# HHKB.net
KiCad netlist of a schematic drawn in EAGLE
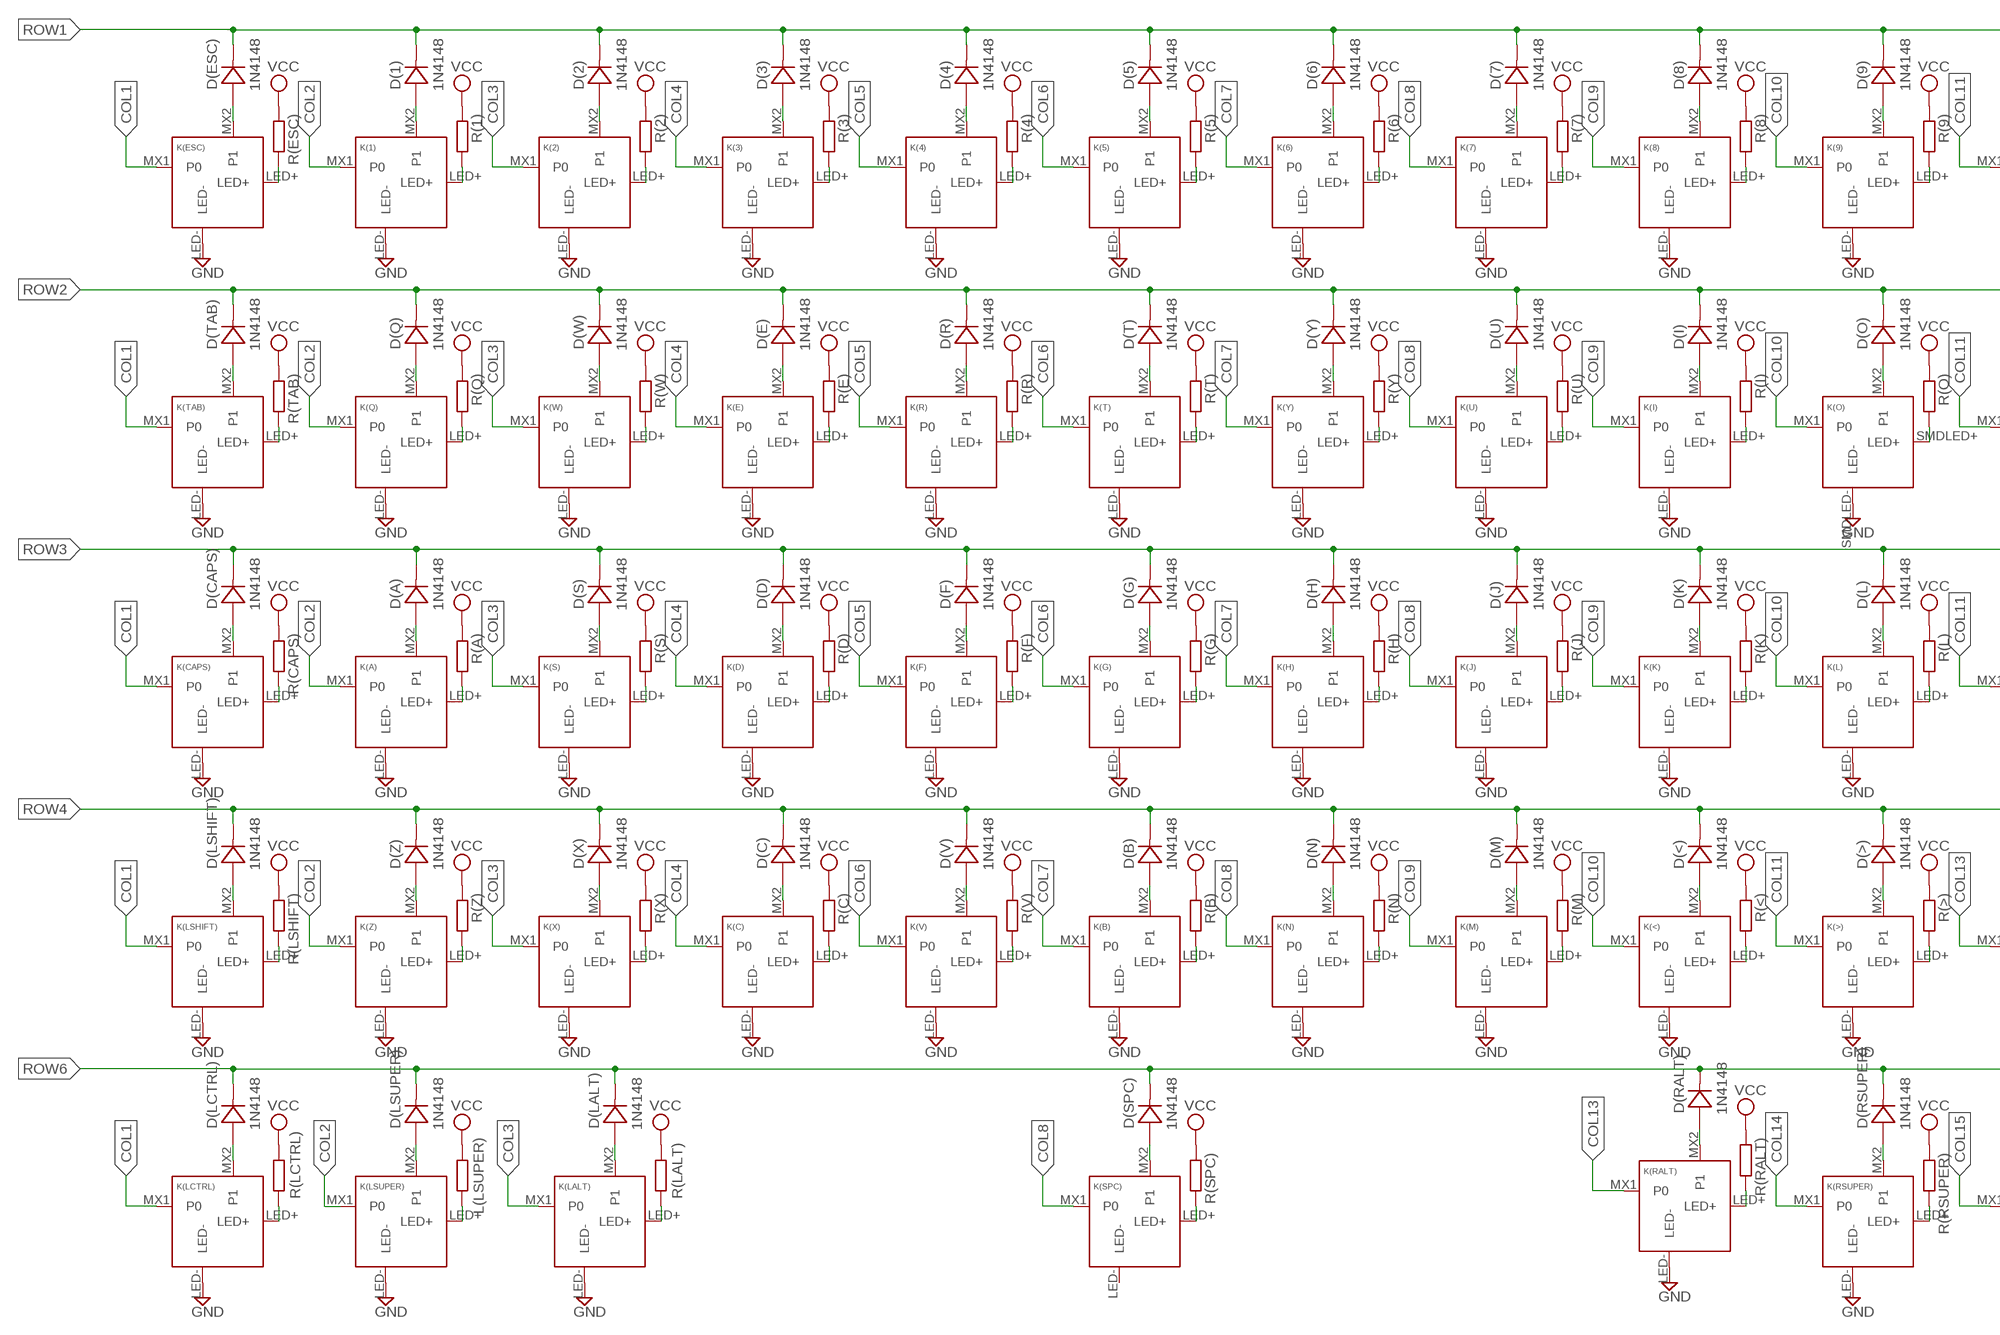
[diagram p0: schematic, sheet 1, part 1 of 2]
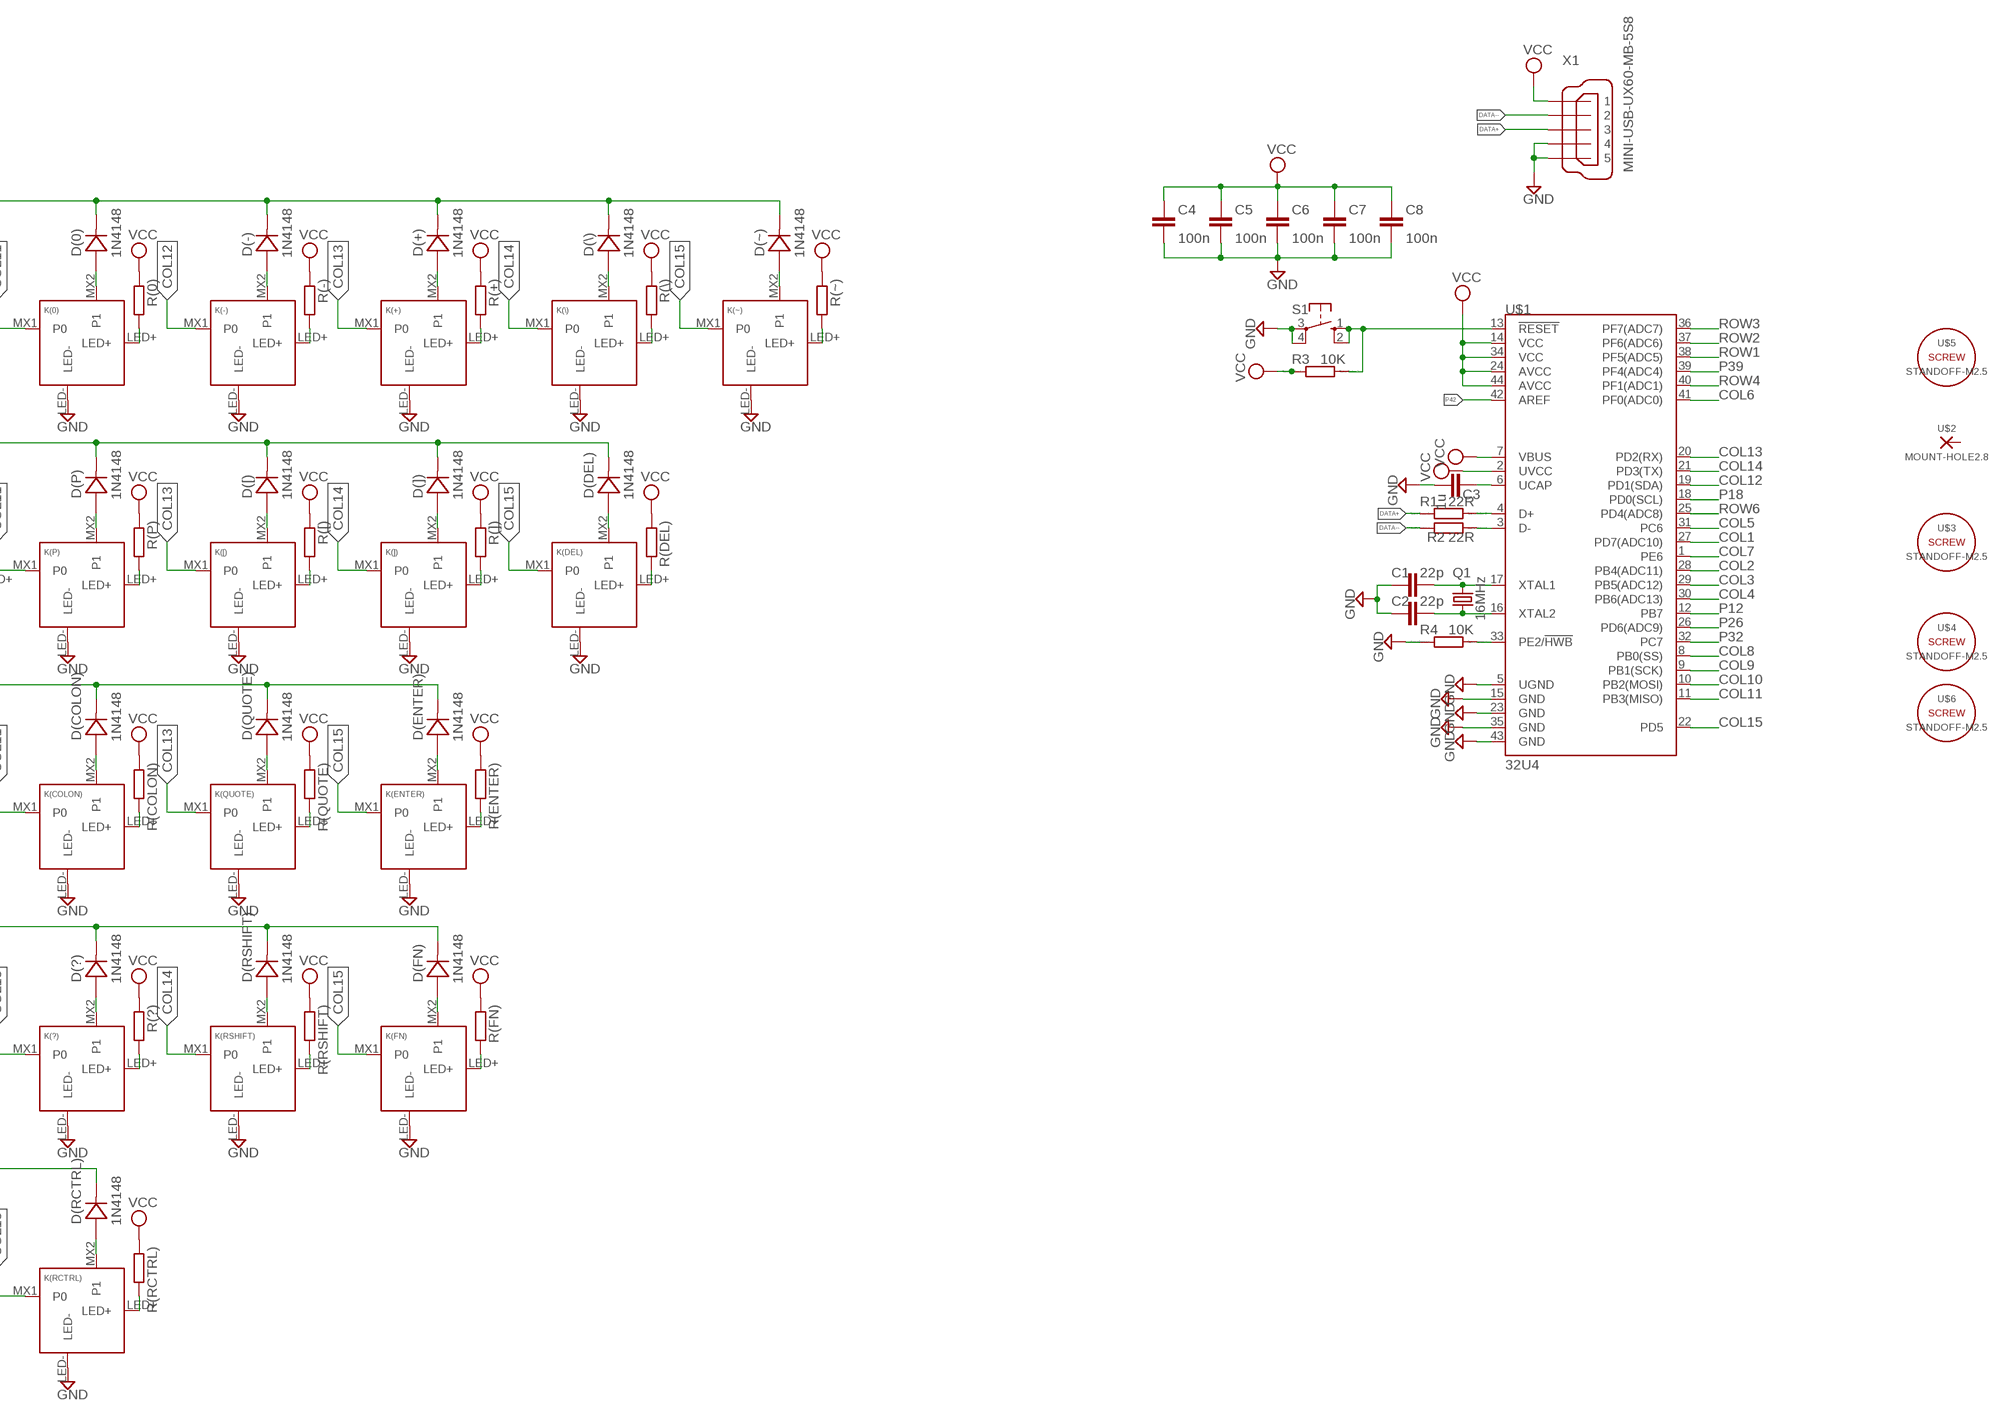
[diagram p1: schematic, sheet 1, part 2 of 2]

(export (version "E")
  (design (tool "Eeschema 10.0.6"))
  (components
    (comp (ref "C1")
      (value "22p")
      (footprint "eagle-import:C0805K")
      (libsource (lib "eagle-import") (part "C-EUC0805K"))
    )
    (comp (ref "C2")
      (value "22p")
      (footprint "eagle-import:C0805K")
      (libsource (lib "eagle-import") (part "C-EUC0805K"))
    )
    (comp (ref "C3")
      (value "1u")
      (footprint "eagle-import:C0805K")
      (libsource (lib "eagle-import") (part "C-EUC0805K"))
    )
    (comp (ref "C4")
      (value "100n")
      (footprint "eagle-import:C0805K")
      (libsource (lib "eagle-import") (part "C-EUC0805K"))
    )
    (comp (ref "C5")
      (value "100n")
      (footprint "eagle-import:C0805K")
      (libsource (lib "eagle-import") (part "C-EUC0805K"))
    )
    (comp (ref "C6")
      (value "100n")
      (footprint "eagle-import:C0805K")
      (libsource (lib "eagle-import") (part "C-EUC0805K"))
    )
    (comp (ref "C7")
      (value "100n")
      (footprint "eagle-import:C0805K")
      (libsource (lib "eagle-import") (part "C-EUC0805K"))
    )
    (comp (ref "C8")
      (value "100n")
      (footprint "eagle-import:C0805K")
      (libsource (lib "eagle-import") (part "C-EUC0805K"))
    )
    (comp (ref "D(+)")
      (value "1N4148")
      (footprint "eagle-import:DIODE_HAND")
      (libsource (lib "eagle-import") (part "DIODE-HAND"))
    )
    (comp (ref "D(-)")
      (value "1N4148")
      (footprint "eagle-import:DIODE_HAND")
      (libsource (lib "eagle-import") (part "DIODE-HAND"))
    )
    (comp (ref "D(0)")
      (value "1N4148")
      (footprint "eagle-import:DIODE_HAND")
      (libsource (lib "eagle-import") (part "DIODE-HAND"))
    )
    (comp (ref "D(1)")
      (value "1N4148")
      (footprint "eagle-import:DIODE_HAND")
      (libsource (lib "eagle-import") (part "DIODE-HAND"))
    )
    (comp (ref "D(2)")
      (value "1N4148")
      (footprint "eagle-import:DIODE_HAND")
      (libsource (lib "eagle-import") (part "DIODE-HAND"))
    )
    (comp (ref "D(3)")
      (value "1N4148")
      (footprint "eagle-import:DIODE_HAND")
      (libsource (lib "eagle-import") (part "DIODE-HAND"))
    )
    (comp (ref "D(4)")
      (value "1N4148")
      (footprint "eagle-import:DIODE_HAND")
      (libsource (lib "eagle-import") (part "DIODE-HAND"))
    )
    (comp (ref "D(5)")
      (value "1N4148")
      (footprint "eagle-import:DIODE_HAND")
      (libsource (lib "eagle-import") (part "DIODE-HAND"))
    )
    (comp (ref "D(6)")
      (value "1N4148")
      (footprint "eagle-import:DIODE_HAND")
      (libsource (lib "eagle-import") (part "DIODE-HAND"))
    )
    (comp (ref "D(7)")
      (value "1N4148")
      (footprint "eagle-import:DIODE_HAND")
      (libsource (lib "eagle-import") (part "DIODE-HAND"))
    )
    (comp (ref "D(8)")
      (value "1N4148")
      (footprint "eagle-import:DIODE_HAND")
      (libsource (lib "eagle-import") (part "DIODE-HAND"))
    )
    (comp (ref "D(9)")
      (value "1N4148")
      (footprint "eagle-import:DIODE_HAND")
      (libsource (lib "eagle-import") (part "DIODE-HAND"))
    )
    (comp (ref "D(<)")
      (value "1N4148")
      (footprint "eagle-import:DIODE_HAND")
      (libsource (lib "eagle-import") (part "DIODE-HAND"))
    )
    (comp (ref "D(>)")
      (value "1N4148")
      (footprint "eagle-import:DIODE_HAND")
      (libsource (lib "eagle-import") (part "DIODE-HAND"))
    )
    (comp (ref "D(?)")
      (value "1N4148")
      (footprint "eagle-import:DIODE_HAND")
      (libsource (lib "eagle-import") (part "DIODE-HAND"))
    )
    (comp (ref "D(A)")
      (value "1N4148")
      (footprint "eagle-import:DIODE_HAND")
      (libsource (lib "eagle-import") (part "DIODE-HAND"))
    )
    (comp (ref "D(B)")
      (value "1N4148")
      (footprint "eagle-import:DIODE_HAND")
      (libsource (lib "eagle-import") (part "DIODE-HAND"))
    )
    (comp (ref "D(C)")
      (value "1N4148")
      (footprint "eagle-import:DIODE_HAND")
      (libsource (lib "eagle-import") (part "DIODE-HAND"))
    )
    (comp (ref "D(CAPS)")
      (value "1N4148")
      (footprint "eagle-import:DIODE_HAND")
      (libsource (lib "eagle-import") (part "DIODE-HAND"))
    )
    (comp (ref "D(COLON)")
      (value "1N4148")
      (footprint "eagle-import:DIODE_HAND")
      (libsource (lib "eagle-import") (part "DIODE-HAND"))
    )
    (comp (ref "D(D)")
      (value "1N4148")
      (footprint "eagle-import:DIODE_HAND")
      (libsource (lib "eagle-import") (part "DIODE-HAND"))
    )
    (comp (ref "D(DEL)")
      (value "1N4148")
      (footprint "eagle-import:DIODE_HAND")
      (libsource (lib "eagle-import") (part "DIODE-HAND"))
    )
    (comp (ref "D(E)")
      (value "1N4148")
      (footprint "eagle-import:DIODE_HAND")
      (libsource (lib "eagle-import") (part "DIODE-HAND"))
    )
    (comp (ref "D(ENTER)")
      (value "1N4148")
      (footprint "eagle-import:DIODE_HAND")
      (libsource (lib "eagle-import") (part "DIODE-HAND"))
    )
    (comp (ref "D(ESC)")
      (value "1N4148")
      (footprint "eagle-import:DIODE_HAND")
      (libsource (lib "eagle-import") (part "DIODE-HAND"))
    )
    (comp (ref "D(F)")
      (value "1N4148")
      (footprint "eagle-import:DIODE_HAND")
      (libsource (lib "eagle-import") (part "DIODE-HAND"))
    )
    (comp (ref "D(FN)")
      (value "1N4148")
      (footprint "eagle-import:DIODE_HAND")
      (libsource (lib "eagle-import") (part "DIODE-HAND"))
    )
    (comp (ref "D(G)")
      (value "1N4148")
      (footprint "eagle-import:DIODE_HAND")
      (libsource (lib "eagle-import") (part "DIODE-HAND"))
    )
    (comp (ref "D(H)")
      (value "1N4148")
      (footprint "eagle-import:DIODE_HAND")
      (libsource (lib "eagle-import") (part "DIODE-HAND"))
    )
    (comp (ref "D(I)")
      (value "1N4148")
      (footprint "eagle-import:DIODE_HAND")
      (libsource (lib "eagle-import") (part "DIODE-HAND"))
    )
    (comp (ref "D(J)")
      (value "1N4148")
      (footprint "eagle-import:DIODE_HAND")
      (libsource (lib "eagle-import") (part "DIODE-HAND"))
    )
    (comp (ref "D(K)")
      (value "1N4148")
      (footprint "eagle-import:DIODE_HAND")
      (libsource (lib "eagle-import") (part "DIODE-HAND"))
    )
    (comp (ref "D(L)")
      (value "1N4148")
      (footprint "eagle-import:DIODE_HAND")
      (libsource (lib "eagle-import") (part "DIODE-HAND"))
    )
    (comp (ref "D(LALT)")
      (value "1N4148")
      (footprint "eagle-import:DIODE_HAND")
      (libsource (lib "eagle-import") (part "DIODE-HAND"))
    )
    (comp (ref "D(LCTRL)")
      (value "1N4148")
      (footprint "eagle-import:DIODE_HAND")
      (libsource (lib "eagle-import") (part "DIODE-HAND"))
    )
    (comp (ref "D(LSHIFT)")
      (value "1N4148")
      (footprint "eagle-import:DIODE_HAND")
      (libsource (lib "eagle-import") (part "DIODE-HAND"))
    )
    (comp (ref "D(LSUPER)")
      (value "1N4148")
      (footprint "eagle-import:DIODE_HAND")
      (libsource (lib "eagle-import") (part "DIODE-HAND"))
    )
    (comp (ref "D(M)")
      (value "1N4148")
      (footprint "eagle-import:DIODE_HAND")
      (libsource (lib "eagle-import") (part "DIODE-HAND"))
    )
    (comp (ref "D(N)")
      (value "1N4148")
      (footprint "eagle-import:DIODE_HAND")
      (libsource (lib "eagle-import") (part "DIODE-HAND"))
    )
    (comp (ref "D(O)")
      (value "1N4148")
      (footprint "eagle-import:DIODE_HAND")
      (libsource (lib "eagle-import") (part "DIODE-HAND"))
    )
    (comp (ref "D(P)")
      (value "1N4148")
      (footprint "eagle-import:DIODE_HAND")
      (libsource (lib "eagle-import") (part "DIODE-HAND"))
    )
    (comp (ref "D(Q)")
      (value "1N4148")
      (footprint "eagle-import:DIODE_HAND")
      (libsource (lib "eagle-import") (part "DIODE-HAND"))
    )
    (comp (ref "D(QUOTE)")
      (value "1N4148")
      (footprint "eagle-import:DIODE_HAND")
      (libsource (lib "eagle-import") (part "DIODE-HAND"))
    )
    (comp (ref "D(R)")
      (value "1N4148")
      (footprint "eagle-import:DIODE_HAND")
      (libsource (lib "eagle-import") (part "DIODE-HAND"))
    )
    (comp (ref "D(RALT)")
      (value "1N4148")
      (footprint "eagle-import:DIODE_HAND")
      (libsource (lib "eagle-import") (part "DIODE-HAND"))
    )
    (comp (ref "D(RCTRL)")
      (value "1N4148")
      (footprint "eagle-import:DIODE_HAND")
      (libsource (lib "eagle-import") (part "DIODE-HAND"))
    )
    (comp (ref "D(RSHIFT)")
      (value "1N4148")
      (footprint "eagle-import:DIODE_HAND")
      (libsource (lib "eagle-import") (part "DIODE-HAND"))
    )
    (comp (ref "D(RSUPER)")
      (value "1N4148")
      (footprint "eagle-import:DIODE_HAND")
      (libsource (lib "eagle-import") (part "DIODE-HAND"))
    )
    (comp (ref "D(S)")
      (value "1N4148")
      (footprint "eagle-import:DIODE_HAND")
      (libsource (lib "eagle-import") (part "DIODE-HAND"))
    )
    (comp (ref "D(SPC)")
      (value "1N4148")
      (footprint "eagle-import:DIODE_HAND")
      (libsource (lib "eagle-import") (part "DIODE-HAND"))
    )
    (comp (ref "D(T)")
      (value "1N4148")
      (footprint "eagle-import:DIODE_HAND")
      (libsource (lib "eagle-import") (part "DIODE-HAND"))
    )
    (comp (ref "D(TAB)")
      (value "1N4148")
      (footprint "eagle-import:DIODE_HAND")
      (libsource (lib "eagle-import") (part "DIODE-HAND"))
    )
    (comp (ref "D(U)")
      (value "1N4148")
      (footprint "eagle-import:DIODE_HAND")
      (libsource (lib "eagle-import") (part "DIODE-HAND"))
    )
    (comp (ref "D(V)")
      (value "1N4148")
      (footprint "eagle-import:DIODE_HAND")
      (libsource (lib "eagle-import") (part "DIODE-HAND"))
    )
    (comp (ref "D(W)")
      (value "1N4148")
      (footprint "eagle-import:DIODE_HAND")
      (libsource (lib "eagle-import") (part "DIODE-HAND"))
    )
    (comp (ref "D(X)")
      (value "1N4148")
      (footprint "eagle-import:DIODE_HAND")
      (libsource (lib "eagle-import") (part "DIODE-HAND"))
    )
    (comp (ref "D(Y)")
      (value "1N4148")
      (footprint "eagle-import:DIODE_HAND")
      (libsource (lib "eagle-import") (part "DIODE-HAND"))
    )
    (comp (ref "D(Z)")
      (value "1N4148")
      (footprint "eagle-import:DIODE_HAND")
      (libsource (lib "eagle-import") (part "DIODE-HAND"))
    )
    (comp (ref "D([)")
      (value "1N4148")
      (footprint "eagle-import:DIODE_HAND")
      (libsource (lib "eagle-import") (part "DIODE-HAND"))
    )
    (comp (ref "D(\\\\)")
      (value "1N4148")
      (footprint "eagle-import:DIODE_HAND")
      (libsource (lib "eagle-import") (part "DIODE-HAND"))
    )
    (comp (ref "D(])")
      (value "1N4148")
      (footprint "eagle-import:DIODE_HAND")
      (libsource (lib "eagle-import") (part "DIODE-HAND"))
    )
    (comp (ref "D(~)")
      (value "1N4148")
      (footprint "eagle-import:DIODE_HAND")
      (libsource (lib "eagle-import") (part "DIODE-HAND"))
    )
    (comp (ref "K(+)")
      (value "KEYSWITCH-LEDTHTHOLE-MXHS-1U-LEDTHTHOLE")
      (footprint "eagle-import:MXHS-1U-LEDTHTHOLE")
      (libsource (lib "eagle-import") (part "KEYSWITCH-LEDTHTHOLE-MXHS-1U-LEDTHTHOLE"))
    )
    (comp (ref "K(-)")
      (value "KEYSWITCH-LEDTHTHOLE-MXHS-1U-LEDTHTHOLE")
      (footprint "eagle-import:MXHS-1U-LEDTHTHOLE")
      (libsource (lib "eagle-import") (part "KEYSWITCH-LEDTHTHOLE-MXHS-1U-LEDTHTHOLE"))
    )
    (comp (ref "K(0)")
      (value "KEYSWITCH-LEDTHTHOLE-MXHS-1U-LEDTHTHOLE")
      (footprint "eagle-import:MXHS-1U-LEDTHTHOLE")
      (libsource (lib "eagle-import") (part "KEYSWITCH-LEDTHTHOLE-MXHS-1U-LEDTHTHOLE"))
    )
    (comp (ref "K(1)")
      (value "KEYSWITCH-LEDTHTHOLE-MXHS-1U-LEDTHTHOLE")
      (footprint "eagle-import:MXHS-1U-LEDTHTHOLE")
      (libsource (lib "eagle-import") (part "KEYSWITCH-LEDTHTHOLE-MXHS-1U-LEDTHTHOLE"))
    )
    (comp (ref "K(2)")
      (value "KEYSWITCH-LEDTHTHOLE-MXHS-1U-LEDTHTHOLE")
      (footprint "eagle-import:MXHS-1U-LEDTHTHOLE")
      (libsource (lib "eagle-import") (part "KEYSWITCH-LEDTHTHOLE-MXHS-1U-LEDTHTHOLE"))
    )
    (comp (ref "K(3)")
      (value "KEYSWITCH-LEDTHTHOLE-MXHS-1U-LEDTHTHOLE")
      (footprint "eagle-import:MXHS-1U-LEDTHTHOLE")
      (libsource (lib "eagle-import") (part "KEYSWITCH-LEDTHTHOLE-MXHS-1U-LEDTHTHOLE"))
    )
    (comp (ref "K(4)")
      (value "KEYSWITCH-LEDTHTHOLE-MXHS-1U-LEDTHTHOLE")
      (footprint "eagle-import:MXHS-1U-LEDTHTHOLE")
      (libsource (lib "eagle-import") (part "KEYSWITCH-LEDTHTHOLE-MXHS-1U-LEDTHTHOLE"))
    )
    (comp (ref "K(5)")
      (value "KEYSWITCH-LEDTHTHOLE-MXHS-1U-LEDTHTHOLE")
      (footprint "eagle-import:MXHS-1U-LEDTHTHOLE")
      (libsource (lib "eagle-import") (part "KEYSWITCH-LEDTHTHOLE-MXHS-1U-LEDTHTHOLE"))
    )
    (comp (ref "K(6)")
      (value "KEYSWITCH-LEDTHTHOLE-MXHS-1U-LEDTHTHOLE")
      (footprint "eagle-import:MXHS-1U-LEDTHTHOLE")
      (libsource (lib "eagle-import") (part "KEYSWITCH-LEDTHTHOLE-MXHS-1U-LEDTHTHOLE"))
    )
    (comp (ref "K(7)")
      (value "KEYSWITCH-LEDTHTHOLE-MXHS-1U-LEDTHTHOLE")
      (footprint "eagle-import:MXHS-1U-LEDTHTHOLE")
      (libsource (lib "eagle-import") (part "KEYSWITCH-LEDTHTHOLE-MXHS-1U-LEDTHTHOLE"))
    )
    (comp (ref "K(8)")
      (value "KEYSWITCH-LEDTHTHOLE-MXHS-1U-LEDTHTHOLE")
      (footprint "eagle-import:MXHS-1U-LEDTHTHOLE")
      (libsource (lib "eagle-import") (part "KEYSWITCH-LEDTHTHOLE-MXHS-1U-LEDTHTHOLE"))
    )
    (comp (ref "K(9)")
      (value "KEYSWITCH-LEDTHTHOLE-MXHS-1U-LEDTHTHOLE")
      (footprint "eagle-import:MXHS-1U-LEDTHTHOLE")
      (libsource (lib "eagle-import") (part "KEYSWITCH-LEDTHTHOLE-MXHS-1U-LEDTHTHOLE"))
    )
    (comp (ref "K(<)")
      (value "KEYSWITCH-LEDTHTHOLE-MXHS-1U-LEDTHTHOLE")
      (footprint "eagle-import:MXHS-1U-LEDTHTHOLE")
      (libsource (lib "eagle-import") (part "KEYSWITCH-LEDTHTHOLE-MXHS-1U-LEDTHTHOLE"))
    )
    (comp (ref "K(>)")
      (value "KEYSWITCH-LEDTHTHOLE-MXHS-1U-LEDTHTHOLE")
      (footprint "eagle-import:MXHS-1U-LEDTHTHOLE")
      (libsource (lib "eagle-import") (part "KEYSWITCH-LEDTHTHOLE-MXHS-1U-LEDTHTHOLE"))
    )
    (comp (ref "K(?)")
      (value "KEYSWITCH-LEDTHTHOLE-MXHS-1U-LEDTHTHOLE")
      (footprint "eagle-import:MXHS-1U-LEDTHTHOLE")
      (libsource (lib "eagle-import") (part "KEYSWITCH-LEDTHTHOLE-MXHS-1U-LEDTHTHOLE"))
    )
    (comp (ref "K(A)")
      (value "KEYSWITCH-LEDTHTHOLE-MXHS-1U-LEDTHTHOLE")
      (footprint "eagle-import:MXHS-1U-LEDTHTHOLE")
      (libsource (lib "eagle-import") (part "KEYSWITCH-LEDTHTHOLE-MXHS-1U-LEDTHTHOLE"))
    )
    (comp (ref "K(B)")
      (value "KEYSWITCH-LEDTHTHOLE-MXHS-1U-LEDTHTHOLE")
      (footprint "eagle-import:MXHS-1U-LEDTHTHOLE")
      (libsource (lib "eagle-import") (part "KEYSWITCH-LEDTHTHOLE-MXHS-1U-LEDTHTHOLE"))
    )
    (comp (ref "K(C)")
      (value "KEYSWITCH-LEDTHTHOLE-MXHS-1U-LEDTHTHOLE")
      (footprint "eagle-import:MXHS-1U-LEDTHTHOLE")
      (libsource (lib "eagle-import") (part "KEYSWITCH-LEDTHTHOLE-MXHS-1U-LEDTHTHOLE"))
    )
    (comp (ref "K(CAPS)")
      (value "KEYSWITCH-LEDTHTHOLE-MXHS-1U-LEDTHTHOLE")
      (footprint "eagle-import:MXHS-1U-LEDTHTHOLE")
      (libsource (lib "eagle-import") (part "KEYSWITCH-LEDTHTHOLE-MXHS-1U-LEDTHTHOLE"))
    )
    (comp (ref "K(COLON)")
      (value "KEYSWITCH-LEDTHTHOLE-MXHS-1U-LEDTHTHOLE")
      (footprint "eagle-import:MXHS-1U-LEDTHTHOLE")
      (libsource (lib "eagle-import") (part "KEYSWITCH-LEDTHTHOLE-MXHS-1U-LEDTHTHOLE"))
    )
    (comp (ref "K(D)")
      (value "KEYSWITCH-LEDTHTHOLE-MXHS-1U-LEDTHTHOLE")
      (footprint "eagle-import:MXHS-1U-LEDTHTHOLE")
      (libsource (lib "eagle-import") (part "KEYSWITCH-LEDTHTHOLE-MXHS-1U-LEDTHTHOLE"))
    )
    (comp (ref "K(DEL)")
      (value "KEYSWITCH-LEDTHTHOLE-MXHS-1U-LEDTHTHOLE")
      (footprint "eagle-import:MXHS-1U-LEDTHTHOLE")
      (libsource (lib "eagle-import") (part "KEYSWITCH-LEDTHTHOLE-MXHS-1U-LEDTHTHOLE"))
    )
    (comp (ref "K(E)")
      (value "KEYSWITCH-LEDTHTHOLE-MXHS-1U-LEDTHTHOLE")
      (footprint "eagle-import:MXHS-1U-LEDTHTHOLE")
      (libsource (lib "eagle-import") (part "KEYSWITCH-LEDTHTHOLE-MXHS-1U-LEDTHTHOLE"))
    )
    (comp (ref "K(ENTER)")
      (value "KEYSWITCH-LEDTHTHOLE-MXHS-2U-LEDTHTHOLE")
      (footprint "eagle-import:MXHS-2U-LEDTHTHOLE")
      (libsource (lib "eagle-import") (part "KEYSWITCH-LEDTHTHOLE-MXHS-2U-LEDTHTHOLE"))
    )
    (comp (ref "K(ESC)")
      (value "KEYSWITCH-LEDTHTHOLE-MXHS-1U-LEDTHTHOLE")
      (footprint "eagle-import:MXHS-1U-LEDTHTHOLE")
      (libsource (lib "eagle-import") (part "KEYSWITCH-LEDTHTHOLE-MXHS-1U-LEDTHTHOLE"))
    )
    (comp (ref "K(F)")
      (value "KEYSWITCH-LEDTHTHOLE-MXHS-1U-LEDTHTHOLE")
      (footprint "eagle-import:MXHS-1U-LEDTHTHOLE")
      (libsource (lib "eagle-import") (part "KEYSWITCH-LEDTHTHOLE-MXHS-1U-LEDTHTHOLE"))
    )
    (comp (ref "K(FN)")
      (value "KEYSWITCH-LEDTHTHOLE-MXHS-1U-LEDTHTHOLE")
      (footprint "eagle-import:MXHS-1U-LEDTHTHOLE")
      (libsource (lib "eagle-import") (part "KEYSWITCH-LEDTHTHOLE-MXHS-1U-LEDTHTHOLE"))
    )
    (comp (ref "K(G)")
      (value "KEYSWITCH-LEDTHTHOLE-MXHS-1U-LEDTHTHOLE")
      (footprint "eagle-import:MXHS-1U-LEDTHTHOLE")
      (libsource (lib "eagle-import") (part "KEYSWITCH-LEDTHTHOLE-MXHS-1U-LEDTHTHOLE"))
    )
    (comp (ref "K(H)")
      (value "KEYSWITCH-LEDTHTHOLE-MXHS-1U-LEDTHTHOLE")
      (footprint "eagle-import:MXHS-1U-LEDTHTHOLE")
      (libsource (lib "eagle-import") (part "KEYSWITCH-LEDTHTHOLE-MXHS-1U-LEDTHTHOLE"))
    )
    (comp (ref "K(I)")
      (value "KEYSWITCH-LEDTHTHOLE-MXHS-1U-LEDTHTHOLE")
      (footprint "eagle-import:MXHS-1U-LEDTHTHOLE")
      (libsource (lib "eagle-import") (part "KEYSWITCH-LEDTHTHOLE-MXHS-1U-LEDTHTHOLE"))
    )
    (comp (ref "K(J)")
      (value "KEYSWITCH-LEDTHTHOLE-MXHS-1U-LEDTHTHOLE")
      (footprint "eagle-import:MXHS-1U-LEDTHTHOLE")
      (libsource (lib "eagle-import") (part "KEYSWITCH-LEDTHTHOLE-MXHS-1U-LEDTHTHOLE"))
    )
    (comp (ref "K(K)")
      (value "KEYSWITCH-LEDTHTHOLE-MXHS-1U-LEDTHTHOLE")
      (footprint "eagle-import:MXHS-1U-LEDTHTHOLE")
      (libsource (lib "eagle-import") (part "KEYSWITCH-LEDTHTHOLE-MXHS-1U-LEDTHTHOLE"))
    )
    (comp (ref "K(L)")
      (value "KEYSWITCH-LEDTHTHOLE-MXHS-1U-LEDTHTHOLE")
      (footprint "eagle-import:MXHS-1U-LEDTHTHOLE")
      (libsource (lib "eagle-import") (part "KEYSWITCH-LEDTHTHOLE-MXHS-1U-LEDTHTHOLE"))
    )
    (comp (ref "K(LALT)")
      (value "KEYSWITCH-LEDTHTHOLE-MXHS-1U-LEDTHTHOLE")
      (footprint "eagle-import:MXHS-1U-LEDTHTHOLE")
      (libsource (lib "eagle-import") (part "KEYSWITCH-LEDTHTHOLE-MXHS-1U-LEDTHTHOLE"))
    )
    (comp (ref "K(LCTRL)")
      (value "KEYSWITCH-LEDTHTHOLE-MXHS-1U-LEDTHTHOLE")
      (footprint "eagle-import:MXHS-1U-LEDTHTHOLE")
      (libsource (lib "eagle-import") (part "KEYSWITCH-LEDTHTHOLE-MXHS-1U-LEDTHTHOLE"))
    )
    (comp (ref "K(LSHIFT)")
      (value "KEYSWITCH-LEDTHTHOLE-MXHS-2U-LEDTHTHOLE")
      (footprint "eagle-import:MXHS-2U-LEDTHTHOLE")
      (libsource (lib "eagle-import") (part "KEYSWITCH-LEDTHTHOLE-MXHS-2U-LEDTHTHOLE"))
    )
    (comp (ref "K(LSUPER)")
      (value "KEYSWITCH-LEDTHTHOLE-MXHS-1U-LEDTHTHOLE")
      (footprint "eagle-import:MXHS-1U-LEDTHTHOLE")
      (libsource (lib "eagle-import") (part "KEYSWITCH-LEDTHTHOLE-MXHS-1U-LEDTHTHOLE"))
    )
    (comp (ref "K(M)")
      (value "KEYSWITCH-LEDTHTHOLE-MXHS-1U-LEDTHTHOLE")
      (footprint "eagle-import:MXHS-1U-LEDTHTHOLE")
      (libsource (lib "eagle-import") (part "KEYSWITCH-LEDTHTHOLE-MXHS-1U-LEDTHTHOLE"))
    )
    (comp (ref "K(N)")
      (value "KEYSWITCH-LEDTHTHOLE-MXHS-1U-LEDTHTHOLE")
      (footprint "eagle-import:MXHS-1U-LEDTHTHOLE")
      (libsource (lib "eagle-import") (part "KEYSWITCH-LEDTHTHOLE-MXHS-1U-LEDTHTHOLE"))
    )
    (comp (ref "K(O)")
      (value "KEYSWITCH-SMDLED-MXHSPCB-1U-SMDLED")
      (footprint "eagle-import:MXHSPCB-1U-SMDLED")
      (libsource (lib "eagle-import") (part "KEYSWITCH-SMDLED-MXHSPCB-1U-SMDLED"))
    )
    (comp (ref "K(P)")
      (value "KEYSWITCH-LEDTHTHOLE-MXHS-1U-LEDTHTHOLE")
      (footprint "eagle-import:MXHS-1U-LEDTHTHOLE")
      (libsource (lib "eagle-import") (part "KEYSWITCH-LEDTHTHOLE-MXHS-1U-LEDTHTHOLE"))
    )
    (comp (ref "K(Q)")
      (value "KEYSWITCH-LEDTHTHOLE-MXHS-1U-LEDTHTHOLE")
      (footprint "eagle-import:MXHS-1U-LEDTHTHOLE")
      (libsource (lib "eagle-import") (part "KEYSWITCH-LEDTHTHOLE-MXHS-1U-LEDTHTHOLE"))
    )
    (comp (ref "K(QUOTE)")
      (value "KEYSWITCH-LEDTHTHOLE-MXHS-1U-LEDTHTHOLE")
      (footprint "eagle-import:MXHS-1U-LEDTHTHOLE")
      (libsource (lib "eagle-import") (part "KEYSWITCH-LEDTHTHOLE-MXHS-1U-LEDTHTHOLE"))
    )
    (comp (ref "K(R)")
      (value "KEYSWITCH-LEDTHTHOLE-MXHS-1U-LEDTHTHOLE")
      (footprint "eagle-import:MXHS-1U-LEDTHTHOLE")
      (libsource (lib "eagle-import") (part "KEYSWITCH-LEDTHTHOLE-MXHS-1U-LEDTHTHOLE"))
    )
    (comp (ref "K(RALT)")
      (value "KEYSWITCH-LEDTHTHOLE-MXHS-1U-LEDTHTHOLE")
      (footprint "eagle-import:MXHS-1U-LEDTHTHOLE")
      (libsource (lib "eagle-import") (part "KEYSWITCH-LEDTHTHOLE-MXHS-1U-LEDTHTHOLE"))
    )
    (comp (ref "K(RCTRL)")
      (value "KEYSWITCH-LEDTHTHOLE-MXHS-1U-LEDTHTHOLE")
      (footprint "eagle-import:MXHS-1U-LEDTHTHOLE")
      (libsource (lib "eagle-import") (part "KEYSWITCH-LEDTHTHOLE-MXHS-1U-LEDTHTHOLE"))
    )
    (comp (ref "K(RSHIFT)")
      (value "KEYSWITCH-LEDTHTHOLE-MXHS-1U-LEDTHTHOLE")
      (footprint "eagle-import:MXHS-1U-LEDTHTHOLE")
      (libsource (lib "eagle-import") (part "KEYSWITCH-LEDTHTHOLE-MXHS-1U-LEDTHTHOLE"))
    )
    (comp (ref "K(RSUPER)")
      (value "KEYSWITCH-LEDTHTHOLE-MXHS-1U-LEDTHTHOLE")
      (footprint "eagle-import:MXHS-1U-LEDTHTHOLE")
      (libsource (lib "eagle-import") (part "KEYSWITCH-LEDTHTHOLE-MXHS-1U-LEDTHTHOLE"))
    )
    (comp (ref "K(S)")
      (value "KEYSWITCH-LEDTHTHOLE-MXHS-1U-LEDTHTHOLE")
      (footprint "eagle-import:MXHS-1U-LEDTHTHOLE")
      (libsource (lib "eagle-import") (part "KEYSWITCH-LEDTHTHOLE-MXHS-1U-LEDTHTHOLE"))
    )
    (comp (ref "K(SPC)")
      (value "KEYSWITCH-LEDTHTHOLE-MXHS-7U-LEDTHTHOLE")
      (footprint "eagle-import:MXHS-7U-LEDTHTHOLE")
      (libsource (lib "eagle-import") (part "KEYSWITCH-LEDTHTHOLE-MXHS-7U-LEDTHTHOLE"))
    )
    (comp (ref "K(T)")
      (value "KEYSWITCH-LEDTHTHOLE-MXHS-1U-LEDTHTHOLE")
      (footprint "eagle-import:MXHS-1U-LEDTHTHOLE")
      (libsource (lib "eagle-import") (part "KEYSWITCH-LEDTHTHOLE-MXHS-1U-LEDTHTHOLE"))
    )
    (comp (ref "K(TAB)")
      (value "KEYSWITCH-LEDTHTHOLE-MXHS-1U-LEDTHTHOLE")
      (footprint "eagle-import:MXHS-1U-LEDTHTHOLE")
      (libsource (lib "eagle-import") (part "KEYSWITCH-LEDTHTHOLE-MXHS-1U-LEDTHTHOLE"))
    )
    (comp (ref "K(U)")
      (value "KEYSWITCH-LEDTHTHOLE-MXHS-1U-LEDTHTHOLE")
      (footprint "eagle-import:MXHS-1U-LEDTHTHOLE")
      (libsource (lib "eagle-import") (part "KEYSWITCH-LEDTHTHOLE-MXHS-1U-LEDTHTHOLE"))
    )
    (comp (ref "K(V)")
      (value "KEYSWITCH-LEDTHTHOLE-MXHS-1U-LEDTHTHOLE")
      (footprint "eagle-import:MXHS-1U-LEDTHTHOLE")
      (libsource (lib "eagle-import") (part "KEYSWITCH-LEDTHTHOLE-MXHS-1U-LEDTHTHOLE"))
    )
    (comp (ref "K(W)")
      (value "KEYSWITCH-LEDTHTHOLE-MXHS-1U-LEDTHTHOLE")
      (footprint "eagle-import:MXHS-1U-LEDTHTHOLE")
      (libsource (lib "eagle-import") (part "KEYSWITCH-LEDTHTHOLE-MXHS-1U-LEDTHTHOLE"))
    )
    (comp (ref "K(X)")
      (value "KEYSWITCH-LEDTHTHOLE-MXHS-1U-LEDTHTHOLE")
      (footprint "eagle-import:MXHS-1U-LEDTHTHOLE")
      (libsource (lib "eagle-import") (part "KEYSWITCH-LEDTHTHOLE-MXHS-1U-LEDTHTHOLE"))
    )
    (comp (ref "K(Y)")
      (value "KEYSWITCH-LEDTHTHOLE-MXHS-1U-LEDTHTHOLE")
      (footprint "eagle-import:MXHS-1U-LEDTHTHOLE")
      (libsource (lib "eagle-import") (part "KEYSWITCH-LEDTHTHOLE-MXHS-1U-LEDTHTHOLE"))
    )
    (comp (ref "K(Z)")
      (value "KEYSWITCH-LEDTHTHOLE-MXHS-1U-LEDTHTHOLE")
      (footprint "eagle-import:MXHS-1U-LEDTHTHOLE")
      (libsource (lib "eagle-import") (part "KEYSWITCH-LEDTHTHOLE-MXHS-1U-LEDTHTHOLE"))
    )
    (comp (ref "K([)")
      (value "KEYSWITCH-LEDTHTHOLE-MXHS-1U-LEDTHTHOLE")
      (footprint "eagle-import:MXHS-1U-LEDTHTHOLE")
      (libsource (lib "eagle-import") (part "KEYSWITCH-LEDTHTHOLE-MXHS-1U-LEDTHTHOLE"))
    )
    (comp (ref "K(\\\\)")
      (value "KEYSWITCH-LEDTHTHOLE-MXHS-1U-LEDTHTHOLE")
      (footprint "eagle-import:MXHS-1U-LEDTHTHOLE")
      (libsource (lib "eagle-import") (part "KEYSWITCH-LEDTHTHOLE-MXHS-1U-LEDTHTHOLE"))
    )
    (comp (ref "K(])")
      (value "KEYSWITCH-LEDTHTHOLE-MXHS-1U-LEDTHTHOLE")
      (footprint "eagle-import:MXHS-1U-LEDTHTHOLE")
      (libsource (lib "eagle-import") (part "KEYSWITCH-LEDTHTHOLE-MXHS-1U-LEDTHTHOLE"))
    )
    (comp (ref "K(~)")
      (value "KEYSWITCH-LEDTHTHOLE-MXHS-1U-LEDTHTHOLE")
      (footprint "eagle-import:MXHS-1U-LEDTHTHOLE")
      (libsource (lib "eagle-import") (part "KEYSWITCH-LEDTHTHOLE-MXHS-1U-LEDTHTHOLE"))
    )
    (comp (ref "L(LSUPER)")
      (value "RESISTOR-THT-SMALL")
      (footprint "eagle-import:THT-RESISTOR-SMALL")
      (libsource (lib "eagle-import") (part "RESISTOR-THT-SMALL"))
    )
    (comp (ref "Q1")
      (value "16MHz")
      (footprint "eagle-import:5.0X3.2_2")
      (libsource (lib "eagle-import") (part "KX-9B"))
    )
    (comp (ref "R(+)")
      (value "RESISTOR-THT-SMALL")
      (footprint "eagle-import:THT-RESISTOR-SMALL")
      (libsource (lib "eagle-import") (part "RESISTOR-THT-SMALL"))
    )
    (comp (ref "R(-)")
      (value "RESISTOR-THT-SMALL")
      (footprint "eagle-import:THT-RESISTOR-SMALL")
      (libsource (lib "eagle-import") (part "RESISTOR-THT-SMALL"))
    )
    (comp (ref "R(0)")
      (value "RESISTOR-THT-SMALL")
      (footprint "eagle-import:THT-RESISTOR-SMALL")
      (libsource (lib "eagle-import") (part "RESISTOR-THT-SMALL"))
    )
    (comp (ref "R(1)")
      (value "RESISTOR-THT-SMALL")
      (footprint "eagle-import:THT-RESISTOR-SMALL")
      (libsource (lib "eagle-import") (part "RESISTOR-THT-SMALL"))
    )
    (comp (ref "R(2)")
      (value "RESISTOR-THT-SMALL")
      (footprint "eagle-import:THT-RESISTOR-SMALL")
      (libsource (lib "eagle-import") (part "RESISTOR-THT-SMALL"))
    )
    (comp (ref "R(3)")
      (value "RESISTOR-THT-SMALL")
      (footprint "eagle-import:THT-RESISTOR-SMALL")
      (libsource (lib "eagle-import") (part "RESISTOR-THT-SMALL"))
    )
    (comp (ref "R(4)")
      (value "RESISTOR-THT-SMALL")
      (footprint "eagle-import:THT-RESISTOR-SMALL")
      (libsource (lib "eagle-import") (part "RESISTOR-THT-SMALL"))
    )
    (comp (ref "R(5)")
      (value "RESISTOR-THT-SMALL")
      (footprint "eagle-import:THT-RESISTOR-SMALL")
      (libsource (lib "eagle-import") (part "RESISTOR-THT-SMALL"))
    )
    (comp (ref "R(6)")
      (value "RESISTOR-THT-SMALL")
      (footprint "eagle-import:THT-RESISTOR-SMALL")
      (libsource (lib "eagle-import") (part "RESISTOR-THT-SMALL"))
    )
    (comp (ref "R(7)")
      (value "RESISTOR-THT-SMALL")
      (footprint "eagle-import:THT-RESISTOR-SMALL")
      (libsource (lib "eagle-import") (part "RESISTOR-THT-SMALL"))
    )
    (comp (ref "R(8)")
      (value "RESISTOR-THT-SMALL")
      (footprint "eagle-import:THT-RESISTOR-SMALL")
      (libsource (lib "eagle-import") (part "RESISTOR-THT-SMALL"))
    )
    (comp (ref "R(9)")
      (value "RESISTOR-THT-SMALL")
      (footprint "eagle-import:THT-RESISTOR-SMALL")
      (libsource (lib "eagle-import") (part "RESISTOR-THT-SMALL"))
    )
    (comp (ref "R(<)")
      (value "RESISTOR-THT-SMALL")
      (footprint "eagle-import:THT-RESISTOR-SMALL")
      (libsource (lib "eagle-import") (part "RESISTOR-THT-SMALL"))
    )
    (comp (ref "R(>)")
      (value "RESISTOR-THT-SMALL")
      (footprint "eagle-import:THT-RESISTOR-SMALL")
      (libsource (lib "eagle-import") (part "RESISTOR-THT-SMALL"))
    )
    (comp (ref "R(?)")
      (value "RESISTOR-THT-SMALL")
      (footprint "eagle-import:THT-RESISTOR-SMALL")
      (libsource (lib "eagle-import") (part "RESISTOR-THT-SMALL"))
    )
    (comp (ref "R(A)")
      (value "RESISTOR-THT-SMALL")
      (footprint "eagle-import:THT-RESISTOR-SMALL")
      (libsource (lib "eagle-import") (part "RESISTOR-THT-SMALL"))
    )
    (comp (ref "R(B)")
      (value "RESISTOR-THT-SMALL")
      (footprint "eagle-import:THT-RESISTOR-SMALL")
      (libsource (lib "eagle-import") (part "RESISTOR-THT-SMALL"))
    )
    (comp (ref "R(C)")
      (value "RESISTOR-THT-SMALL")
      (footprint "eagle-import:THT-RESISTOR-SMALL")
      (libsource (lib "eagle-import") (part "RESISTOR-THT-SMALL"))
    )
    (comp (ref "R(CAPS)")
      (value "RESISTOR-THT-SMALL")
      (footprint "eagle-import:THT-RESISTOR-SMALL")
      (libsource (lib "eagle-import") (part "RESISTOR-THT-SMALL"))
    )
    (comp (ref "R(COLON)")
      (value "RESISTOR-THT-SMALL")
      (footprint "eagle-import:THT-RESISTOR-SMALL")
      (libsource (lib "eagle-import") (part "RESISTOR-THT-SMALL"))
    )
    (comp (ref "R(D)")
      (value "RESISTOR-THT-SMALL")
      (footprint "eagle-import:THT-RESISTOR-SMALL")
      (libsource (lib "eagle-import") (part "RESISTOR-THT-SMALL"))
    )
    (comp (ref "R(DEL)")
      (value "RESISTOR-THT-SMALL")
      (footprint "eagle-import:THT-RESISTOR-SMALL")
      (libsource (lib "eagle-import") (part "RESISTOR-THT-SMALL"))
    )
    (comp (ref "R(E)")
      (value "RESISTOR-THT-SMALL")
      (footprint "eagle-import:THT-RESISTOR-SMALL")
      (libsource (lib "eagle-import") (part "RESISTOR-THT-SMALL"))
    )
    (comp (ref "R(ENTER)")
      (value "RESISTOR-THT-SMALL")
      (footprint "eagle-import:THT-RESISTOR-SMALL")
      (libsource (lib "eagle-import") (part "RESISTOR-THT-SMALL"))
    )
    (comp (ref "R(ESC)")
      (value "RESISTOR-THT-SMALL")
      (footprint "eagle-import:THT-RESISTOR-SMALL")
      (libsource (lib "eagle-import") (part "RESISTOR-THT-SMALL"))
    )
    (comp (ref "R(F)")
      (value "RESISTOR-THT-SMALL")
      (footprint "eagle-import:THT-RESISTOR-SMALL")
      (libsource (lib "eagle-import") (part "RESISTOR-THT-SMALL"))
    )
    (comp (ref "R(FN)")
      (value "RESISTOR-THT-SMALL")
      (footprint "eagle-import:THT-RESISTOR-SMALL")
      (libsource (lib "eagle-import") (part "RESISTOR-THT-SMALL"))
    )
    (comp (ref "R(G)")
      (value "RESISTOR-THT-SMALL")
      (footprint "eagle-import:THT-RESISTOR-SMALL")
      (libsource (lib "eagle-import") (part "RESISTOR-THT-SMALL"))
    )
    (comp (ref "R(H)")
      (value "RESISTOR-THT-SMALL")
      (footprint "eagle-import:THT-RESISTOR-SMALL")
      (libsource (lib "eagle-import") (part "RESISTOR-THT-SMALL"))
    )
    (comp (ref "R(I)")
      (value "RESISTOR-THT-SMALL")
      (footprint "eagle-import:THT-RESISTOR-SMALL")
      (libsource (lib "eagle-import") (part "RESISTOR-THT-SMALL"))
    )
    (comp (ref "R(J)")
      (value "RESISTOR-THT-SMALL")
      (footprint "eagle-import:THT-RESISTOR-SMALL")
      (libsource (lib "eagle-import") (part "RESISTOR-THT-SMALL"))
    )
    (comp (ref "R(K)")
      (value "RESISTOR-THT-SMALL")
      (footprint "eagle-import:THT-RESISTOR-SMALL")
      (libsource (lib "eagle-import") (part "RESISTOR-THT-SMALL"))
    )
    (comp (ref "R(L)")
      (value "RESISTOR-THT-SMALL")
      (footprint "eagle-import:THT-RESISTOR-SMALL")
      (libsource (lib "eagle-import") (part "RESISTOR-THT-SMALL"))
    )
    (comp (ref "R(LALT)")
      (value "RESISTOR-THT-SMALL")
      (footprint "eagle-import:THT-RESISTOR-SMALL")
      (libsource (lib "eagle-import") (part "RESISTOR-THT-SMALL"))
    )
    (comp (ref "R(LCTRL)")
      (value "RESISTOR-THT-SMALL")
      (footprint "eagle-import:THT-RESISTOR-SMALL")
      (libsource (lib "eagle-import") (part "RESISTOR-THT-SMALL"))
    )
    (comp (ref "R(LSHIFT)")
      (value "RESISTOR-THT-SMALL")
      (footprint "eagle-import:THT-RESISTOR-SMALL")
      (libsource (lib "eagle-import") (part "RESISTOR-THT-SMALL"))
    )
    (comp (ref "R(M)")
      (value "RESISTOR-THT-SMALL")
      (footprint "eagle-import:THT-RESISTOR-SMALL")
      (libsource (lib "eagle-import") (part "RESISTOR-THT-SMALL"))
    )
    (comp (ref "R(N)")
      (value "RESISTOR-THT-SMALL")
      (footprint "eagle-import:THT-RESISTOR-SMALL")
      (libsource (lib "eagle-import") (part "RESISTOR-THT-SMALL"))
    )
    (comp (ref "R(O)")
      (value "RESISTOR-THT-SMALL")
      (footprint "eagle-import:THT-RESISTOR-SMALL")
      (libsource (lib "eagle-import") (part "RESISTOR-THT-SMALL"))
    )
    (comp (ref "R(P)")
      (value "RESISTOR-THT-SMALL")
      (footprint "eagle-import:THT-RESISTOR-SMALL")
      (libsource (lib "eagle-import") (part "RESISTOR-THT-SMALL"))
    )
    (comp (ref "R(Q)")
      (value "RESISTOR-THT-SMALL")
      (footprint "eagle-import:THT-RESISTOR-SMALL")
      (libsource (lib "eagle-import") (part "RESISTOR-THT-SMALL"))
    )
    (comp (ref "R(QUOTE)")
      (value "RESISTOR-THT-SMALL")
      (footprint "eagle-import:THT-RESISTOR-SMALL")
      (libsource (lib "eagle-import") (part "RESISTOR-THT-SMALL"))
    )
    (comp (ref "R(R)")
      (value "RESISTOR-THT-SMALL")
      (footprint "eagle-import:THT-RESISTOR-SMALL")
      (libsource (lib "eagle-import") (part "RESISTOR-THT-SMALL"))
    )
    (comp (ref "R(RALT)")
      (value "RESISTOR-THT-SMALL")
      (footprint "eagle-import:THT-RESISTOR-SMALL")
      (libsource (lib "eagle-import") (part "RESISTOR-THT-SMALL"))
    )
    (comp (ref "R(RCTRL)")
      (value "RESISTOR-THT-SMALL")
      (footprint "eagle-import:THT-RESISTOR-SMALL")
      (libsource (lib "eagle-import") (part "RESISTOR-THT-SMALL"))
    )
    (comp (ref "R(RSHIFT)")
      (value "RESISTOR-THT-SMALL")
      (footprint "eagle-import:THT-RESISTOR-SMALL")
      (libsource (lib "eagle-import") (part "RESISTOR-THT-SMALL"))
    )
    (comp (ref "R(RSUPER)")
      (value "RESISTOR-THT-SMALL")
      (footprint "eagle-import:THT-RESISTOR-SMALL")
      (libsource (lib "eagle-import") (part "RESISTOR-THT-SMALL"))
    )
    (comp (ref "R(S)")
      (value "RESISTOR-THT-SMALL")
      (footprint "eagle-import:THT-RESISTOR-SMALL")
      (libsource (lib "eagle-import") (part "RESISTOR-THT-SMALL"))
    )
    (comp (ref "R(SPC)")
      (value "RESISTOR-THT-SMALL")
      (footprint "eagle-import:THT-RESISTOR-SMALL")
      (libsource (lib "eagle-import") (part "RESISTOR-THT-SMALL"))
    )
    (comp (ref "R(T)")
      (value "RESISTOR-THT-SMALL")
      (footprint "eagle-import:THT-RESISTOR-SMALL")
      (libsource (lib "eagle-import") (part "RESISTOR-THT-SMALL"))
    )
    (comp (ref "R(TAB)")
      (value "RESISTOR-THT-SMALL")
      (footprint "eagle-import:THT-RESISTOR-SMALL")
      (libsource (lib "eagle-import") (part "RESISTOR-THT-SMALL"))
    )
    (comp (ref "R(U)")
      (value "RESISTOR-THT-SMALL")
      (footprint "eagle-import:THT-RESISTOR-SMALL")
      (libsource (lib "eagle-import") (part "RESISTOR-THT-SMALL"))
    )
    (comp (ref "R(V)")
      (value "RESISTOR-THT-SMALL")
      (footprint "eagle-import:THT-RESISTOR-SMALL")
      (libsource (lib "eagle-import") (part "RESISTOR-THT-SMALL"))
    )
    (comp (ref "R(W)")
      (value "RESISTOR-THT-SMALL")
      (footprint "eagle-import:THT-RESISTOR-SMALL")
      (libsource (lib "eagle-import") (part "RESISTOR-THT-SMALL"))
    )
    (comp (ref "R(X)")
      (value "RESISTOR-THT-SMALL")
      (footprint "eagle-import:THT-RESISTOR-SMALL")
      (libsource (lib "eagle-import") (part "RESISTOR-THT-SMALL"))
    )
    (comp (ref "R(Y)")
      (value "RESISTOR-THT-SMALL")
      (footprint "eagle-import:THT-RESISTOR-SMALL")
      (libsource (lib "eagle-import") (part "RESISTOR-THT-SMALL"))
    )
    (comp (ref "R(Z)")
      (value "RESISTOR-THT-SMALL")
      (footprint "eagle-import:THT-RESISTOR-SMALL")
      (libsource (lib "eagle-import") (part "RESISTOR-THT-SMALL"))
    )
    (comp (ref "R([)")
      (value "RESISTOR-THT-SMALL")
      (footprint "eagle-import:THT-RESISTOR-SMALL")
      (libsource (lib "eagle-import") (part "RESISTOR-THT-SMALL"))
    )
    (comp (ref "R(\\\\)")
      (value "RESISTOR-THT-SMALL")
      (footprint "eagle-import:THT-RESISTOR-SMALL")
      (libsource (lib "eagle-import") (part "RESISTOR-THT-SMALL"))
    )
    (comp (ref "R(])")
      (value "RESISTOR-THT-SMALL")
      (footprint "eagle-import:THT-RESISTOR-SMALL")
      (libsource (lib "eagle-import") (part "RESISTOR-THT-SMALL"))
    )
    (comp (ref "R(~)")
      (value "RESISTOR-THT-SMALL")
      (footprint "eagle-import:THT-RESISTOR-SMALL")
      (libsource (lib "eagle-import") (part "RESISTOR-THT-SMALL"))
    )
    (comp (ref "R1")
      (value "22R")
      (footprint "eagle-import:R1206")
      (libsource (lib "eagle-import") (part "RR1206"))
    )
    (comp (ref "R2")
      (value "22R")
      (footprint "eagle-import:R1206")
      (libsource (lib "eagle-import") (part "RR1206"))
    )
    (comp (ref "R3")
      (value "10K")
      (footprint "eagle-import:R1206")
      (libsource (lib "eagle-import") (part "RR1206"))
    )
    (comp (ref "R4")
      (value "10K")
      (footprint "eagle-import:R1206")
      (libsource (lib "eagle-import") (part "RR1206"))
    )
    (comp (ref "S1")
      (value "10-XX")
      (footprint "eagle-import:B3F-10XX")
      (fields (field (name "MPN") "B3F-1000"))
      (libsource (lib "eagle-import") (part "10-XX"))
    )
    (comp (ref "U$1")
      (value "32U4")
      (footprint "eagle-import:TQFP44")
      (libsource (lib "eagle-import") (part "ATMEGA32U4TQFP-44"))
    )
    (comp (ref "U$2")
      (value "MOUNT-HOLE2.8")
      (footprint "eagle-import:2,54_1,0")
      (libsource (lib "eagle-import") (part "2,54/1,0"))
    )
    (comp (ref "U$3")
      (value "STANDOFF-M2.5")
      (footprint "eagle-import:STANDOFF-M2.5")
      (libsource (lib "eagle-import") (part "STANDOFF-M2.5"))
    )
    (comp (ref "U$4")
      (value "STANDOFF-M2.5")
      (footprint "eagle-import:STANDOFF-M2.5")
      (libsource (lib "eagle-import") (part "STANDOFF-M2.5"))
    )
    (comp (ref "U$5")
      (value "STANDOFF-M2.5")
      (footprint "eagle-import:STANDOFF-M2.5")
      (libsource (lib "eagle-import") (part "STANDOFF-M2.5"))
    )
    (comp (ref "U$6")
      (value "STANDOFF-M2.5")
      (footprint "eagle-import:STANDOFF-M2.5")
      (libsource (lib "eagle-import") (part "STANDOFF-M2.5"))
    )
    (comp (ref "X1")
      (value "MINI-USB-UX60-MB-5S8")
      (footprint "eagle-import:UX60-MB-5S8")
      (libsource (lib "eagle-import") (part "MINI-USB-UX60-MB-5S8"))
    )
  )
  (nets
    (net (code "1") (name "/P12") (class "Default")
      (node (ref "U$1") (pin "12") (pinfunction "PB7_12") (pintype "bidirectional"))
    )
    (net (code "2") (name "/P18") (class "Default")
      (node (ref "U$1") (pin "18") (pinfunction "PD0(SCL)_18") (pintype "bidirectional"))
    )
    (net (code "3") (name "/P26") (class "Default")
      (node (ref "U$1") (pin "26") (pinfunction "PD6(ADC9)_26") (pintype "bidirectional"))
    )
    (net (code "4") (name "/P32") (class "Default")
      (node (ref "U$1") (pin "32") (pinfunction "PC7_32") (pintype "bidirectional"))
    )
    (net (code "5") (name "/P39") (class "Default")
      (node (ref "U$1") (pin "39") (pinfunction "PF4(ADC4)_39") (pintype "bidirectional"))
    )
    (net (code "6") (name "COL1") (class "Default")
      (node (ref "K(CAPS)") (pin "MX1") (pinfunction "P0_MX1") (pintype "bidirectional"))
      (node (ref "K(ESC)") (pin "MX1") (pinfunction "P0_MX1") (pintype "bidirectional"))
      (node (ref "K(LCTRL)") (pin "MX1") (pinfunction "P0_MX1") (pintype "bidirectional"))
      (node (ref "K(LSHIFT)") (pin "MX1") (pinfunction "P0_MX1") (pintype "bidirectional"))
      (node (ref "K(TAB)") (pin "MX1") (pinfunction "P0_MX1") (pintype "bidirectional"))
      (node (ref "U$1") (pin "27") (pinfunction "PD7(ADC10)_27") (pintype "bidirectional"))
    )
    (net (code "7") (name "COL2") (class "Default")
      (node (ref "K(1)") (pin "MX1") (pinfunction "P0_MX1") (pintype "bidirectional"))
      (node (ref "K(A)") (pin "MX1") (pinfunction "P0_MX1") (pintype "bidirectional"))
      (node (ref "K(LSUPER)") (pin "MX1") (pinfunction "P0_MX1") (pintype "bidirectional"))
      (node (ref "K(Q)") (pin "MX1") (pinfunction "P0_MX1") (pintype "bidirectional"))
      (node (ref "K(Z)") (pin "MX1") (pinfunction "P0_MX1") (pintype "bidirectional"))
      (node (ref "U$1") (pin "28") (pinfunction "PB4(ADC11)_28") (pintype "bidirectional"))
    )
    (net (code "8") (name "COL3") (class "Default")
      (node (ref "K(2)") (pin "MX1") (pinfunction "P0_MX1") (pintype "bidirectional"))
      (node (ref "K(LALT)") (pin "MX1") (pinfunction "P0_MX1") (pintype "bidirectional"))
      (node (ref "K(S)") (pin "MX1") (pinfunction "P0_MX1") (pintype "bidirectional"))
      (node (ref "K(W)") (pin "MX1") (pinfunction "P0_MX1") (pintype "bidirectional"))
      (node (ref "K(X)") (pin "MX1") (pinfunction "P0_MX1") (pintype "bidirectional"))
      (node (ref "U$1") (pin "29") (pinfunction "PB5(ADC12)_29") (pintype "bidirectional"))
    )
    (net (code "9") (name "COL4") (class "Default")
      (node (ref "K(3)") (pin "MX1") (pinfunction "P0_MX1") (pintype "bidirectional"))
      (node (ref "K(C)") (pin "MX1") (pinfunction "P0_MX1") (pintype "bidirectional"))
      (node (ref "K(D)") (pin "MX1") (pinfunction "P0_MX1") (pintype "bidirectional"))
      (node (ref "K(E)") (pin "MX1") (pinfunction "P0_MX1") (pintype "bidirectional"))
      (node (ref "U$1") (pin "30") (pinfunction "PB6(ADC13)_30") (pintype "bidirectional"))
    )
    (net (code "10") (name "COL5") (class "Default")
      (node (ref "K(4)") (pin "MX1") (pinfunction "P0_MX1") (pintype "bidirectional"))
      (node (ref "K(F)") (pin "MX1") (pinfunction "P0_MX1") (pintype "bidirectional"))
      (node (ref "K(R)") (pin "MX1") (pinfunction "P0_MX1") (pintype "bidirectional"))
      (node (ref "U$1") (pin "31") (pinfunction "PC6_31") (pintype "bidirectional"))
    )
    (net (code "11") (name "COL6") (class "Default")
      (node (ref "K(5)") (pin "MX1") (pinfunction "P0_MX1") (pintype "bidirectional"))
      (node (ref "K(G)") (pin "MX1") (pinfunction "P0_MX1") (pintype "bidirectional"))
      (node (ref "K(T)") (pin "MX1") (pinfunction "P0_MX1") (pintype "bidirectional"))
      (node (ref "K(V)") (pin "MX1") (pinfunction "P0_MX1") (pintype "bidirectional"))
      (node (ref "U$1") (pin "41") (pinfunction "PF0(ADC0)_41") (pintype "bidirectional"))
    )
    (net (code "12") (name "COL7") (class "Default")
      (node (ref "K(6)") (pin "MX1") (pinfunction "P0_MX1") (pintype "bidirectional"))
      (node (ref "K(B)") (pin "MX1") (pinfunction "P0_MX1") (pintype "bidirectional"))
      (node (ref "K(H)") (pin "MX1") (pinfunction "P0_MX1") (pintype "bidirectional"))
      (node (ref "K(Y)") (pin "MX1") (pinfunction "P0_MX1") (pintype "bidirectional"))
      (node (ref "U$1") (pin "1") (pinfunction "PE6_1") (pintype "bidirectional"))
    )
    (net (code "13") (name "COL8") (class "Default")
      (node (ref "K(7)") (pin "MX1") (pinfunction "P0_MX1") (pintype "bidirectional"))
      (node (ref "K(J)") (pin "MX1") (pinfunction "P0_MX1") (pintype "bidirectional"))
      (node (ref "K(N)") (pin "MX1") (pinfunction "P0_MX1") (pintype "bidirectional"))
      (node (ref "K(SPC)") (pin "MX1") (pinfunction "P0_MX1") (pintype "bidirectional"))
      (node (ref "K(U)") (pin "MX1") (pinfunction "P0_MX1") (pintype "bidirectional"))
      (node (ref "U$1") (pin "8") (pinfunction "PB0(SS)_8") (pintype "bidirectional"))
    )
    (net (code "14") (name "COL9") (class "Default")
      (node (ref "K(8)") (pin "MX1") (pinfunction "P0_MX1") (pintype "bidirectional"))
      (node (ref "K(I)") (pin "MX1") (pinfunction "P0_MX1") (pintype "bidirectional"))
      (node (ref "K(K)") (pin "MX1") (pinfunction "P0_MX1") (pintype "bidirectional"))
      (node (ref "K(M)") (pin "MX1") (pinfunction "P0_MX1") (pintype "bidirectional"))
      (node (ref "U$1") (pin "9") (pinfunction "PB1(SCK)_9") (pintype "bidirectional"))
    )
    (net (code "15") (name "COL10") (class "Default")
      (node (ref "K(9)") (pin "MX1") (pinfunction "P0_MX1") (pintype "bidirectional"))
      (node (ref "K(<)") (pin "MX1") (pinfunction "P0_MX1") (pintype "bidirectional"))
      (node (ref "K(L)") (pin "MX1") (pinfunction "P0_MX1") (pintype "bidirectional"))
      (node (ref "K(O)") (pin "MX1") (pinfunction "P0_MX1") (pintype "bidirectional"))
      (node (ref "U$1") (pin "10") (pinfunction "PB2(MOSI)_10") (pintype "bidirectional"))
    )
    (net (code "16") (name "COL11") (class "Default")
      (node (ref "K(0)") (pin "MX1") (pinfunction "P0_MX1") (pintype "bidirectional"))
      (node (ref "K(>)") (pin "MX1") (pinfunction "P0_MX1") (pintype "bidirectional"))
      (node (ref "K(COLON)") (pin "MX1") (pinfunction "P0_MX1") (pintype "bidirectional"))
      (node (ref "K(P)") (pin "MX1") (pinfunction "P0_MX1") (pintype "bidirectional"))
      (node (ref "U$1") (pin "11") (pinfunction "PB3(MISO)_11") (pintype "bidirectional"))
    )
    (net (code "17") (name "COL12") (class "Default")
      (node (ref "K(-)") (pin "MX1") (pinfunction "P0_MX1") (pintype "bidirectional"))
      (node (ref "U$1") (pin "19") (pinfunction "PD1(SDA)_19") (pintype "bidirectional"))
    )
    (net (code "18") (name "COL13") (class "Default")
      (node (ref "K(+)") (pin "MX1") (pinfunction "P0_MX1") (pintype "bidirectional"))
      (node (ref "K(?)") (pin "MX1") (pinfunction "P0_MX1") (pintype "bidirectional"))
      (node (ref "K(QUOTE)") (pin "MX1") (pinfunction "P0_MX1") (pintype "bidirectional"))
      (node (ref "K(RALT)") (pin "MX1") (pinfunction "P0_MX1") (pintype "bidirectional"))
      (node (ref "K([)") (pin "MX1") (pinfunction "P0_MX1") (pintype "bidirectional"))
      (node (ref "U$1") (pin "20") (pinfunction "PD2(RX)_20") (pintype "bidirectional"))
    )
    (net (code "19") (name "COL14") (class "Default")
      (node (ref "K(RSHIFT)") (pin "MX1") (pinfunction "P0_MX1") (pintype "bidirectional"))
      (node (ref "K(RSUPER)") (pin "MX1") (pinfunction "P0_MX1") (pintype "bidirectional"))
      (node (ref "K(\\\\)") (pin "MX1") (pinfunction "P0_MX1") (pintype "bidirectional"))
      (node (ref "K(])") (pin "MX1") (pinfunction "P0_MX1") (pintype "bidirectional"))
      (node (ref "U$1") (pin "21") (pinfunction "PD3(TX)_21") (pintype "bidirectional"))
    )
    (net (code "20") (name "COL15") (class "Default")
      (node (ref "K(DEL)") (pin "MX1") (pinfunction "P0_MX1") (pintype "bidirectional"))
      (node (ref "K(ENTER)") (pin "MX1") (pinfunction "P0_MX1") (pintype "bidirectional"))
      (node (ref "K(FN)") (pin "MX1") (pinfunction "P0_MX1") (pintype "bidirectional"))
      (node (ref "K(RCTRL)") (pin "MX1") (pinfunction "P0_MX1") (pintype "bidirectional"))
      (node (ref "K(~)") (pin "MX1") (pinfunction "P0_MX1") (pintype "bidirectional"))
      (node (ref "U$1") (pin "22") (pinfunction "PD5_22") (pintype "bidirectional"))
    )
    (net (code "21") (name "DATA+") (class "Default")
      (node (ref "R1") (pin "1") (pinfunction "1_1") (pintype "passive"))
      (node (ref "X1") (pin "3") (pinfunction "3_3") (pintype "input"))
    )
    (net (code "22") (name "DATA--") (class "Default")
      (node (ref "R2") (pin "1") (pinfunction "1_1") (pintype "passive"))
      (node (ref "X1") (pin "2") (pinfunction "2_2") (pintype "input"))
    )
    (net (code "23") (name "GND") (class "Default")
      (node (ref "C1") (pin "2") (pinfunction "2_2") (pintype "passive"))
      (node (ref "C2") (pin "2") (pinfunction "2_2") (pintype "passive"))
      (node (ref "C3") (pin "2") (pinfunction "2_2") (pintype "passive"))
      (node (ref "C4") (pin "2") (pinfunction "2_2") (pintype "passive"))
      (node (ref "C5") (pin "2") (pinfunction "2_2") (pintype "passive"))
      (node (ref "C6") (pin "2") (pinfunction "2_2") (pintype "passive"))
      (node (ref "C7") (pin "2") (pinfunction "2_2") (pintype "passive"))
      (node (ref "C8") (pin "2") (pinfunction "2_2") (pintype "passive"))
      (node (ref "K(+)") (pin "LED-") (pinfunction "LED-_LED-") (pintype "bidirectional"))
      (node (ref "K(-)") (pin "LED-") (pinfunction "LED-_LED-") (pintype "bidirectional"))
      (node (ref "K(0)") (pin "LED-") (pinfunction "LED-_LED-") (pintype "bidirectional"))
      (node (ref "K(1)") (pin "LED-") (pinfunction "LED-_LED-") (pintype "bidirectional"))
      (node (ref "K(2)") (pin "LED-") (pinfunction "LED-_LED-") (pintype "bidirectional"))
      (node (ref "K(3)") (pin "LED-") (pinfunction "LED-_LED-") (pintype "bidirectional"))
      (node (ref "K(4)") (pin "LED-") (pinfunction "LED-_LED-") (pintype "bidirectional"))
      (node (ref "K(5)") (pin "LED-") (pinfunction "LED-_LED-") (pintype "bidirectional"))
      (node (ref "K(6)") (pin "LED-") (pinfunction "LED-_LED-") (pintype "bidirectional"))
      (node (ref "K(7)") (pin "LED-") (pinfunction "LED-_LED-") (pintype "bidirectional"))
      (node (ref "K(8)") (pin "LED-") (pinfunction "LED-_LED-") (pintype "bidirectional"))
      (node (ref "K(9)") (pin "LED-") (pinfunction "LED-_LED-") (pintype "bidirectional"))
      (node (ref "K(<)") (pin "LED-") (pinfunction "LED-_LED-") (pintype "bidirectional"))
      (node (ref "K(>)") (pin "LED-") (pinfunction "LED-_LED-") (pintype "bidirectional"))
      (node (ref "K(?)") (pin "LED-") (pinfunction "LED-_LED-") (pintype "bidirectional"))
      (node (ref "K(A)") (pin "LED-") (pinfunction "LED-_LED-") (pintype "bidirectional"))
      (node (ref "K(B)") (pin "LED-") (pinfunction "LED-_LED-") (pintype "bidirectional"))
      (node (ref "K(C)") (pin "LED-") (pinfunction "LED-_LED-") (pintype "bidirectional"))
      (node (ref "K(CAPS)") (pin "LED-") (pinfunction "LED-_LED-") (pintype "bidirectional"))
      (node (ref "K(COLON)") (pin "LED-") (pinfunction "LED-_LED-") (pintype "bidirectional"))
      (node (ref "K(D)") (pin "LED-") (pinfunction "LED-_LED-") (pintype "bidirectional"))
      (node (ref "K(DEL)") (pin "LED-") (pinfunction "LED-_LED-") (pintype "bidirectional"))
      (node (ref "K(E)") (pin "LED-") (pinfunction "LED-_LED-") (pintype "bidirectional"))
      (node (ref "K(ENTER)") (pin "LED-") (pinfunction "LED-_LED-") (pintype "bidirectional"))
      (node (ref "K(ESC)") (pin "LED-") (pinfunction "LED-_LED-") (pintype "bidirectional"))
      (node (ref "K(F)") (pin "LED-") (pinfunction "LED-_LED-") (pintype "bidirectional"))
      (node (ref "K(FN)") (pin "LED-") (pinfunction "LED-_LED-") (pintype "bidirectional"))
      (node (ref "K(G)") (pin "LED-") (pinfunction "LED-_LED-") (pintype "bidirectional"))
      (node (ref "K(H)") (pin "LED-") (pinfunction "LED-_LED-") (pintype "bidirectional"))
      (node (ref "K(I)") (pin "LED-") (pinfunction "LED-_LED-") (pintype "bidirectional"))
      (node (ref "K(J)") (pin "LED-") (pinfunction "LED-_LED-") (pintype "bidirectional"))
      (node (ref "K(K)") (pin "LED-") (pinfunction "LED-_LED-") (pintype "bidirectional"))
      (node (ref "K(L)") (pin "LED-") (pinfunction "LED-_LED-") (pintype "bidirectional"))
      (node (ref "K(LALT)") (pin "LED-") (pinfunction "LED-_LED-") (pintype "bidirectional"))
      (node (ref "K(LCTRL)") (pin "LED-") (pinfunction "LED-_LED-") (pintype "bidirectional"))
      (node (ref "K(LSHIFT)") (pin "LED-") (pinfunction "LED-_LED-") (pintype "bidirectional"))
      (node (ref "K(LSUPER)") (pin "LED-") (pinfunction "LED-_LED-") (pintype "bidirectional"))
      (node (ref "K(M)") (pin "LED-") (pinfunction "LED-_LED-") (pintype "bidirectional"))
      (node (ref "K(N)") (pin "LED-") (pinfunction "LED-_LED-") (pintype "bidirectional"))
      (node (ref "K(O)") (pin "SMDLED-") (pinfunction "LED-_SMDLED-") (pintype "bidirectional"))
      (node (ref "K(P)") (pin "LED-") (pinfunction "LED-_LED-") (pintype "bidirectional"))
      (node (ref "K(Q)") (pin "LED-") (pinfunction "LED-_LED-") (pintype "bidirectional"))
      (node (ref "K(QUOTE)") (pin "LED-") (pinfunction "LED-_LED-") (pintype "bidirectional"))
      (node (ref "K(R)") (pin "LED-") (pinfunction "LED-_LED-") (pintype "bidirectional"))
      (node (ref "K(RALT)") (pin "LED-") (pinfunction "LED-_LED-") (pintype "bidirectional"))
      (node (ref "K(RCTRL)") (pin "LED-") (pinfunction "LED-_LED-") (pintype "bidirectional"))
      (node (ref "K(RSHIFT)") (pin "LED-") (pinfunction "LED-_LED-") (pintype "bidirectional"))
      (node (ref "K(RSUPER)") (pin "LED-") (pinfunction "LED-_LED-") (pintype "bidirectional"))
      (node (ref "K(S)") (pin "LED-") (pinfunction "LED-_LED-") (pintype "bidirectional"))
      (node (ref "K(T)") (pin "LED-") (pinfunction "LED-_LED-") (pintype "bidirectional"))
      (node (ref "K(TAB)") (pin "LED-") (pinfunction "LED-_LED-") (pintype "bidirectional"))
      (node (ref "K(U)") (pin "LED-") (pinfunction "LED-_LED-") (pintype "bidirectional"))
      (node (ref "K(V)") (pin "LED-") (pinfunction "LED-_LED-") (pintype "bidirectional"))
      (node (ref "K(W)") (pin "LED-") (pinfunction "LED-_LED-") (pintype "bidirectional"))
      (node (ref "K(X)") (pin "LED-") (pinfunction "LED-_LED-") (pintype "bidirectional"))
      (node (ref "K(Y)") (pin "LED-") (pinfunction "LED-_LED-") (pintype "bidirectional"))
      (node (ref "K(Z)") (pin "LED-") (pinfunction "LED-_LED-") (pintype "bidirectional"))
      (node (ref "K([)") (pin "LED-") (pinfunction "LED-_LED-") (pintype "bidirectional"))
      (node (ref "K(\\\\)") (pin "LED-") (pinfunction "LED-_LED-") (pintype "bidirectional"))
      (node (ref "K(])") (pin "LED-") (pinfunction "LED-_LED-") (pintype "bidirectional"))
      (node (ref "K(~)") (pin "LED-") (pinfunction "LED-_LED-") (pintype "bidirectional"))
      (node (ref "R4") (pin "1") (pinfunction "1_1") (pintype "passive"))
      (node (ref "S1") (pin "3") (pinfunction "P_3") (pintype "passive"))
      (node (ref "S1") (pin "4") (pinfunction "P1_4") (pintype "passive"))
      (node (ref "U$1") (pin "15") (pinfunction "GND_15") (pintype "bidirectional"))
      (node (ref "U$1") (pin "23") (pinfunction "GND_23") (pintype "bidirectional"))
      (node (ref "U$1") (pin "35") (pinfunction "GND_35") (pintype "bidirectional"))
      (node (ref "U$1") (pin "43") (pinfunction "GND_43") (pintype "bidirectional"))
      (node (ref "U$1") (pin "5") (pinfunction "UGND_5") (pintype "bidirectional"))
      (node (ref "X1") (pin "4") (pinfunction "4_4") (pintype "input"))
      (node (ref "X1") (pin "5") (pinfunction "5_5") (pintype "input"))
    )
    (net (code "24") (name "Net-(K(+)-P1)") (class "Default")
      (node (ref "D(+)") (pin "A1") (pinfunction "A_A1") (pintype "passive"))
      (node (ref "D(+)") (pin "A2") (pinfunction "A_A2") (pintype "passive"))
      (node (ref "D(+)") (pin "A3") (pinfunction "A_A3") (pintype "passive"))
      (node (ref "K(+)") (pin "MX2") (pinfunction "P1_MX2") (pintype "bidirectional"))
    )
    (net (code "25") (name "Net-(K(+)-PadLED+)") (class "Default")
      (node (ref "K(+)") (pin "LED+") (pinfunction "LED+_LED+") (pintype "bidirectional"))
      (node (ref "R(+)") (pin "B1") (pinfunction "2_B1") (pintype "passive"))
      (node (ref "R(+)") (pin "B2") (pinfunction "2_B2") (pintype "passive"))
      (node (ref "R(+)") (pin "B3") (pinfunction "2_B3") (pintype "passive"))
    )
    (net (code "26") (name "Net-(K(-)-P1)") (class "Default")
      (node (ref "D(-)") (pin "A1") (pinfunction "A_A1") (pintype "passive"))
      (node (ref "D(-)") (pin "A2") (pinfunction "A_A2") (pintype "passive"))
      (node (ref "D(-)") (pin "A3") (pinfunction "A_A3") (pintype "passive"))
      (node (ref "K(-)") (pin "MX2") (pinfunction "P1_MX2") (pintype "bidirectional"))
    )
    (net (code "27") (name "Net-(K(-)-PadLED+)") (class "Default")
      (node (ref "K(-)") (pin "LED+") (pinfunction "LED+_LED+") (pintype "bidirectional"))
      (node (ref "R(-)") (pin "B1") (pinfunction "2_B1") (pintype "passive"))
      (node (ref "R(-)") (pin "B2") (pinfunction "2_B2") (pintype "passive"))
      (node (ref "R(-)") (pin "B3") (pinfunction "2_B3") (pintype "passive"))
    )
    (net (code "28") (name "Net-(K(0)-P1)") (class "Default")
      (node (ref "D(0)") (pin "A1") (pinfunction "A_A1") (pintype "passive"))
      (node (ref "D(0)") (pin "A2") (pinfunction "A_A2") (pintype "passive"))
      (node (ref "D(0)") (pin "A3") (pinfunction "A_A3") (pintype "passive"))
      (node (ref "K(0)") (pin "MX2") (pinfunction "P1_MX2") (pintype "bidirectional"))
    )
    (net (code "29") (name "Net-(K(0)-PadLED+)") (class "Default")
      (node (ref "K(0)") (pin "LED+") (pinfunction "LED+_LED+") (pintype "bidirectional"))
      (node (ref "R(0)") (pin "B1") (pinfunction "2_B1") (pintype "passive"))
      (node (ref "R(0)") (pin "B2") (pinfunction "2_B2") (pintype "passive"))
      (node (ref "R(0)") (pin "B3") (pinfunction "2_B3") (pintype "passive"))
    )
    (net (code "30") (name "Net-(K(1)-P1)") (class "Default")
      (node (ref "D(1)") (pin "A1") (pinfunction "A_A1") (pintype "passive"))
      (node (ref "D(1)") (pin "A2") (pinfunction "A_A2") (pintype "passive"))
      (node (ref "D(1)") (pin "A3") (pinfunction "A_A3") (pintype "passive"))
      (node (ref "K(1)") (pin "MX2") (pinfunction "P1_MX2") (pintype "bidirectional"))
    )
    (net (code "31") (name "Net-(K(1)-PadLED+)") (class "Default")
      (node (ref "K(1)") (pin "LED+") (pinfunction "LED+_LED+") (pintype "bidirectional"))
      (node (ref "R(1)") (pin "B1") (pinfunction "2_B1") (pintype "passive"))
      (node (ref "R(1)") (pin "B2") (pinfunction "2_B2") (pintype "passive"))
      (node (ref "R(1)") (pin "B3") (pinfunction "2_B3") (pintype "passive"))
    )
    (net (code "32") (name "Net-(K(2)-P1)") (class "Default")
      (node (ref "D(2)") (pin "A1") (pinfunction "A_A1") (pintype "passive"))
      (node (ref "D(2)") (pin "A2") (pinfunction "A_A2") (pintype "passive"))
      (node (ref "D(2)") (pin "A3") (pinfunction "A_A3") (pintype "passive"))
      (node (ref "K(2)") (pin "MX2") (pinfunction "P1_MX2") (pintype "bidirectional"))
    )
    (net (code "33") (name "Net-(K(2)-PadLED+)") (class "Default")
      (node (ref "K(2)") (pin "LED+") (pinfunction "LED+_LED+") (pintype "bidirectional"))
      (node (ref "R(2)") (pin "B1") (pinfunction "2_B1") (pintype "passive"))
      (node (ref "R(2)") (pin "B2") (pinfunction "2_B2") (pintype "passive"))
      (node (ref "R(2)") (pin "B3") (pinfunction "2_B3") (pintype "passive"))
    )
    (net (code "34") (name "Net-(K(3)-P1)") (class "Default")
      (node (ref "D(3)") (pin "A1") (pinfunction "A_A1") (pintype "passive"))
      (node (ref "D(3)") (pin "A2") (pinfunction "A_A2") (pintype "passive"))
      (node (ref "D(3)") (pin "A3") (pinfunction "A_A3") (pintype "passive"))
      (node (ref "K(3)") (pin "MX2") (pinfunction "P1_MX2") (pintype "bidirectional"))
    )
    (net (code "35") (name "Net-(K(3)-PadLED+)") (class "Default")
      (node (ref "K(3)") (pin "LED+") (pinfunction "LED+_LED+") (pintype "bidirectional"))
      (node (ref "R(3)") (pin "B1") (pinfunction "2_B1") (pintype "passive"))
      (node (ref "R(3)") (pin "B2") (pinfunction "2_B2") (pintype "passive"))
      (node (ref "R(3)") (pin "B3") (pinfunction "2_B3") (pintype "passive"))
    )
    (net (code "36") (name "Net-(K(4)-P1)") (class "Default")
      (node (ref "D(4)") (pin "A1") (pinfunction "A_A1") (pintype "passive"))
      (node (ref "D(4)") (pin "A2") (pinfunction "A_A2") (pintype "passive"))
      (node (ref "D(4)") (pin "A3") (pinfunction "A_A3") (pintype "passive"))
      (node (ref "K(4)") (pin "MX2") (pinfunction "P1_MX2") (pintype "bidirectional"))
    )
    (net (code "37") (name "Net-(K(4)-PadLED+)") (class "Default")
      (node (ref "K(4)") (pin "LED+") (pinfunction "LED+_LED+") (pintype "bidirectional"))
      (node (ref "R(4)") (pin "B1") (pinfunction "2_B1") (pintype "passive"))
      (node (ref "R(4)") (pin "B2") (pinfunction "2_B2") (pintype "passive"))
      (node (ref "R(4)") (pin "B3") (pinfunction "2_B3") (pintype "passive"))
    )
    (net (code "38") (name "Net-(K(5)-P1)") (class "Default")
      (node (ref "D(5)") (pin "A1") (pinfunction "A_A1") (pintype "passive"))
      (node (ref "D(5)") (pin "A2") (pinfunction "A_A2") (pintype "passive"))
      (node (ref "D(5)") (pin "A3") (pinfunction "A_A3") (pintype "passive"))
      (node (ref "K(5)") (pin "MX2") (pinfunction "P1_MX2") (pintype "bidirectional"))
    )
    (net (code "39") (name "Net-(K(5)-PadLED+)") (class "Default")
      (node (ref "K(5)") (pin "LED+") (pinfunction "LED+_LED+") (pintype "bidirectional"))
      (node (ref "R(5)") (pin "B1") (pinfunction "2_B1") (pintype "passive"))
      (node (ref "R(5)") (pin "B2") (pinfunction "2_B2") (pintype "passive"))
      (node (ref "R(5)") (pin "B3") (pinfunction "2_B3") (pintype "passive"))
    )
    (net (code "40") (name "Net-(K(6)-P1)") (class "Default")
      (node (ref "D(6)") (pin "A1") (pinfunction "A_A1") (pintype "passive"))
      (node (ref "D(6)") (pin "A2") (pinfunction "A_A2") (pintype "passive"))
      (node (ref "D(6)") (pin "A3") (pinfunction "A_A3") (pintype "passive"))
      (node (ref "K(6)") (pin "MX2") (pinfunction "P1_MX2") (pintype "bidirectional"))
    )
    (net (code "41") (name "Net-(K(6)-PadLED+)") (class "Default")
      (node (ref "K(6)") (pin "LED+") (pinfunction "LED+_LED+") (pintype "bidirectional"))
      (node (ref "R(6)") (pin "B1") (pinfunction "2_B1") (pintype "passive"))
      (node (ref "R(6)") (pin "B2") (pinfunction "2_B2") (pintype "passive"))
      (node (ref "R(6)") (pin "B3") (pinfunction "2_B3") (pintype "passive"))
    )
    (net (code "42") (name "Net-(K(7)-P1)") (class "Default")
      (node (ref "D(7)") (pin "A1") (pinfunction "A_A1") (pintype "passive"))
      (node (ref "D(7)") (pin "A2") (pinfunction "A_A2") (pintype "passive"))
      (node (ref "D(7)") (pin "A3") (pinfunction "A_A3") (pintype "passive"))
      (node (ref "K(7)") (pin "MX2") (pinfunction "P1_MX2") (pintype "bidirectional"))
    )
    (net (code "43") (name "Net-(K(7)-PadLED+)") (class "Default")
      (node (ref "K(7)") (pin "LED+") (pinfunction "LED+_LED+") (pintype "bidirectional"))
      (node (ref "R(7)") (pin "B1") (pinfunction "2_B1") (pintype "passive"))
      (node (ref "R(7)") (pin "B2") (pinfunction "2_B2") (pintype "passive"))
      (node (ref "R(7)") (pin "B3") (pinfunction "2_B3") (pintype "passive"))
    )
    (net (code "44") (name "Net-(K(8)-P1)") (class "Default")
      (node (ref "D(8)") (pin "A1") (pinfunction "A_A1") (pintype "passive"))
      (node (ref "D(8)") (pin "A2") (pinfunction "A_A2") (pintype "passive"))
      (node (ref "D(8)") (pin "A3") (pinfunction "A_A3") (pintype "passive"))
      (node (ref "K(8)") (pin "MX2") (pinfunction "P1_MX2") (pintype "bidirectional"))
    )
    (net (code "45") (name "Net-(K(8)-PadLED+)") (class "Default")
      (node (ref "K(8)") (pin "LED+") (pinfunction "LED+_LED+") (pintype "bidirectional"))
      (node (ref "R(8)") (pin "B1") (pinfunction "2_B1") (pintype "passive"))
      (node (ref "R(8)") (pin "B2") (pinfunction "2_B2") (pintype "passive"))
      (node (ref "R(8)") (pin "B3") (pinfunction "2_B3") (pintype "passive"))
    )
    (net (code "46") (name "Net-(K(9)-P1)") (class "Default")
      (node (ref "D(9)") (pin "A1") (pinfunction "A_A1") (pintype "passive"))
      (node (ref "D(9)") (pin "A2") (pinfunction "A_A2") (pintype "passive"))
      (node (ref "D(9)") (pin "A3") (pinfunction "A_A3") (pintype "passive"))
      (node (ref "K(9)") (pin "MX2") (pinfunction "P1_MX2") (pintype "bidirectional"))
    )
    (net (code "47") (name "Net-(K(9)-PadLED+)") (class "Default")
      (node (ref "K(9)") (pin "LED+") (pinfunction "LED+_LED+") (pintype "bidirectional"))
      (node (ref "R(9)") (pin "B1") (pinfunction "2_B1") (pintype "passive"))
      (node (ref "R(9)") (pin "B2") (pinfunction "2_B2") (pintype "passive"))
      (node (ref "R(9)") (pin "B3") (pinfunction "2_B3") (pintype "passive"))
    )
    (net (code "48") (name "Net-(K(<)-P1)") (class "Default")
      (node (ref "D(<)") (pin "A1") (pinfunction "A_A1") (pintype "passive"))
      (node (ref "D(<)") (pin "A2") (pinfunction "A_A2") (pintype "passive"))
      (node (ref "D(<)") (pin "A3") (pinfunction "A_A3") (pintype "passive"))
      (node (ref "K(<)") (pin "MX2") (pinfunction "P1_MX2") (pintype "bidirectional"))
    )
    (net (code "49") (name "Net-(K(<)-PadLED+)") (class "Default")
      (node (ref "K(<)") (pin "LED+") (pinfunction "LED+_LED+") (pintype "bidirectional"))
      (node (ref "R(<)") (pin "B1") (pinfunction "2_B1") (pintype "passive"))
      (node (ref "R(<)") (pin "B2") (pinfunction "2_B2") (pintype "passive"))
      (node (ref "R(<)") (pin "B3") (pinfunction "2_B3") (pintype "passive"))
    )
    (net (code "50") (name "Net-(K(>)-P1)") (class "Default")
      (node (ref "D(>)") (pin "A1") (pinfunction "A_A1") (pintype "passive"))
      (node (ref "D(>)") (pin "A2") (pinfunction "A_A2") (pintype "passive"))
      (node (ref "D(>)") (pin "A3") (pinfunction "A_A3") (pintype "passive"))
      (node (ref "K(>)") (pin "MX2") (pinfunction "P1_MX2") (pintype "bidirectional"))
    )
    (net (code "51") (name "Net-(K(>)-PadLED+)") (class "Default")
      (node (ref "K(>)") (pin "LED+") (pinfunction "LED+_LED+") (pintype "bidirectional"))
      (node (ref "R(>)") (pin "B1") (pinfunction "2_B1") (pintype "passive"))
      (node (ref "R(>)") (pin "B2") (pinfunction "2_B2") (pintype "passive"))
      (node (ref "R(>)") (pin "B3") (pinfunction "2_B3") (pintype "passive"))
    )
    (net (code "52") (name "Net-(K(?)-P1)") (class "Default")
      (node (ref "D(?)") (pin "A1") (pinfunction "A_A1") (pintype "passive"))
      (node (ref "D(?)") (pin "A2") (pinfunction "A_A2") (pintype "passive"))
      (node (ref "D(?)") (pin "A3") (pinfunction "A_A3") (pintype "passive"))
      (node (ref "K(?)") (pin "MX2") (pinfunction "P1_MX2") (pintype "bidirectional"))
    )
    (net (code "53") (name "Net-(K(?)-PadLED+)") (class "Default")
      (node (ref "K(?)") (pin "LED+") (pinfunction "LED+_LED+") (pintype "bidirectional"))
      (node (ref "R(?)") (pin "B1") (pinfunction "2_B1") (pintype "passive"))
      (node (ref "R(?)") (pin "B2") (pinfunction "2_B2") (pintype "passive"))
      (node (ref "R(?)") (pin "B3") (pinfunction "2_B3") (pintype "passive"))
    )
    (net (code "54") (name "Net-(K(A)-P1)") (class "Default")
      (node (ref "D(A)") (pin "A1") (pinfunction "A_A1") (pintype "passive"))
      (node (ref "D(A)") (pin "A2") (pinfunction "A_A2") (pintype "passive"))
      (node (ref "D(A)") (pin "A3") (pinfunction "A_A3") (pintype "passive"))
      (node (ref "K(A)") (pin "MX2") (pinfunction "P1_MX2") (pintype "bidirectional"))
    )
    (net (code "55") (name "Net-(K(A)-PadLED+)") (class "Default")
      (node (ref "K(A)") (pin "LED+") (pinfunction "LED+_LED+") (pintype "bidirectional"))
      (node (ref "R(A)") (pin "B1") (pinfunction "2_B1") (pintype "passive"))
      (node (ref "R(A)") (pin "B2") (pinfunction "2_B2") (pintype "passive"))
      (node (ref "R(A)") (pin "B3") (pinfunction "2_B3") (pintype "passive"))
    )
    (net (code "56") (name "Net-(K(B)-P1)") (class "Default")
      (node (ref "D(B)") (pin "A1") (pinfunction "A_A1") (pintype "passive"))
      (node (ref "D(B)") (pin "A2") (pinfunction "A_A2") (pintype "passive"))
      (node (ref "D(B)") (pin "A3") (pinfunction "A_A3") (pintype "passive"))
      (node (ref "K(B)") (pin "MX2") (pinfunction "P1_MX2") (pintype "bidirectional"))
    )
    (net (code "57") (name "Net-(K(B)-PadLED+)") (class "Default")
      (node (ref "K(B)") (pin "LED+") (pinfunction "LED+_LED+") (pintype "bidirectional"))
      (node (ref "R(B)") (pin "B1") (pinfunction "2_B1") (pintype "passive"))
      (node (ref "R(B)") (pin "B2") (pinfunction "2_B2") (pintype "passive"))
      (node (ref "R(B)") (pin "B3") (pinfunction "2_B3") (pintype "passive"))
    )
    (net (code "58") (name "Net-(K(C)-P1)") (class "Default")
      (node (ref "D(C)") (pin "A1") (pinfunction "A_A1") (pintype "passive"))
      (node (ref "D(C)") (pin "A2") (pinfunction "A_A2") (pintype "passive"))
      (node (ref "D(C)") (pin "A3") (pinfunction "A_A3") (pintype "passive"))
      (node (ref "K(C)") (pin "MX2") (pinfunction "P1_MX2") (pintype "bidirectional"))
    )
    (net (code "59") (name "Net-(K(C)-PadLED+)") (class "Default")
      (node (ref "K(C)") (pin "LED+") (pinfunction "LED+_LED+") (pintype "bidirectional"))
      (node (ref "R(C)") (pin "B1") (pinfunction "2_B1") (pintype "passive"))
      (node (ref "R(C)") (pin "B2") (pinfunction "2_B2") (pintype "passive"))
      (node (ref "R(C)") (pin "B3") (pinfunction "2_B3") (pintype "passive"))
    )
    (net (code "60") (name "Net-(K(CAPS)-P1)") (class "Default")
      (node (ref "D(CAPS)") (pin "A1") (pinfunction "A_A1") (pintype "passive"))
      (node (ref "D(CAPS)") (pin "A2") (pinfunction "A_A2") (pintype "passive"))
      (node (ref "D(CAPS)") (pin "A3") (pinfunction "A_A3") (pintype "passive"))
      (node (ref "K(CAPS)") (pin "MX2") (pinfunction "P1_MX2") (pintype "bidirectional"))
    )
    (net (code "61") (name "Net-(K(CAPS)-PadLED+)") (class "Default")
      (node (ref "K(CAPS)") (pin "LED+") (pinfunction "LED+_LED+") (pintype "bidirectional"))
      (node (ref "R(CAPS)") (pin "B1") (pinfunction "2_B1") (pintype "passive"))
      (node (ref "R(CAPS)") (pin "B2") (pinfunction "2_B2") (pintype "passive"))
      (node (ref "R(CAPS)") (pin "B3") (pinfunction "2_B3") (pintype "passive"))
    )
    (net (code "62") (name "Net-(K(COLON)-P1)") (class "Default")
      (node (ref "D(COLON)") (pin "A1") (pinfunction "A_A1") (pintype "passive"))
      (node (ref "D(COLON)") (pin "A2") (pinfunction "A_A2") (pintype "passive"))
      (node (ref "D(COLON)") (pin "A3") (pinfunction "A_A3") (pintype "passive"))
      (node (ref "K(COLON)") (pin "MX2") (pinfunction "P1_MX2") (pintype "bidirectional"))
    )
    (net (code "63") (name "Net-(K(COLON)-PadLED+)") (class "Default")
      (node (ref "K(COLON)") (pin "LED+") (pinfunction "LED+_LED+") (pintype "bidirectional"))
      (node (ref "R(COLON)") (pin "B1") (pinfunction "2_B1") (pintype "passive"))
      (node (ref "R(COLON)") (pin "B2") (pinfunction "2_B2") (pintype "passive"))
      (node (ref "R(COLON)") (pin "B3") (pinfunction "2_B3") (pintype "passive"))
    )
    (net (code "64") (name "Net-(K(D)-P1)") (class "Default")
      (node (ref "D(D)") (pin "A1") (pinfunction "A_A1") (pintype "passive"))
      (node (ref "D(D)") (pin "A2") (pinfunction "A_A2") (pintype "passive"))
      (node (ref "D(D)") (pin "A3") (pinfunction "A_A3") (pintype "passive"))
      (node (ref "K(D)") (pin "MX2") (pinfunction "P1_MX2") (pintype "bidirectional"))
    )
    (net (code "65") (name "Net-(K(D)-PadLED+)") (class "Default")
      (node (ref "K(D)") (pin "LED+") (pinfunction "LED+_LED+") (pintype "bidirectional"))
      (node (ref "R(D)") (pin "B1") (pinfunction "2_B1") (pintype "passive"))
      (node (ref "R(D)") (pin "B2") (pinfunction "2_B2") (pintype "passive"))
      (node (ref "R(D)") (pin "B3") (pinfunction "2_B3") (pintype "passive"))
    )
    (net (code "66") (name "Net-(K(DEL)-P1)") (class "Default")
      (node (ref "D(DEL)") (pin "A1") (pinfunction "A_A1") (pintype "passive"))
      (node (ref "D(DEL)") (pin "A2") (pinfunction "A_A2") (pintype "passive"))
      (node (ref "D(DEL)") (pin "A3") (pinfunction "A_A3") (pintype "passive"))
      (node (ref "K(DEL)") (pin "MX2") (pinfunction "P1_MX2") (pintype "bidirectional"))
    )
    (net (code "67") (name "Net-(K(DEL)-PadLED+)") (class "Default")
      (node (ref "K(DEL)") (pin "LED+") (pinfunction "LED+_LED+") (pintype "bidirectional"))
      (node (ref "R(DEL)") (pin "B1") (pinfunction "2_B1") (pintype "passive"))
      (node (ref "R(DEL)") (pin "B2") (pinfunction "2_B2") (pintype "passive"))
      (node (ref "R(DEL)") (pin "B3") (pinfunction "2_B3") (pintype "passive"))
    )
    (net (code "68") (name "Net-(K(E)-P1)") (class "Default")
      (node (ref "D(E)") (pin "A1") (pinfunction "A_A1") (pintype "passive"))
      (node (ref "D(E)") (pin "A2") (pinfunction "A_A2") (pintype "passive"))
      (node (ref "D(E)") (pin "A3") (pinfunction "A_A3") (pintype "passive"))
      (node (ref "K(E)") (pin "MX2") (pinfunction "P1_MX2") (pintype "bidirectional"))
    )
    (net (code "69") (name "Net-(K(E)-PadLED+)") (class "Default")
      (node (ref "K(E)") (pin "LED+") (pinfunction "LED+_LED+") (pintype "bidirectional"))
      (node (ref "R(E)") (pin "B1") (pinfunction "2_B1") (pintype "passive"))
      (node (ref "R(E)") (pin "B2") (pinfunction "2_B2") (pintype "passive"))
      (node (ref "R(E)") (pin "B3") (pinfunction "2_B3") (pintype "passive"))
    )
    (net (code "70") (name "Net-(K(ENTER)-P1)") (class "Default")
      (node (ref "D(ENTER)") (pin "A1") (pinfunction "A_A1") (pintype "passive"))
      (node (ref "D(ENTER)") (pin "A2") (pinfunction "A_A2") (pintype "passive"))
      (node (ref "D(ENTER)") (pin "A3") (pinfunction "A_A3") (pintype "passive"))
      (node (ref "K(ENTER)") (pin "MX2") (pinfunction "P1_MX2") (pintype "bidirectional"))
    )
    (net (code "71") (name "Net-(K(ENTER)-PadLED+)") (class "Default")
      (node (ref "K(ENTER)") (pin "LED+") (pinfunction "LED+_LED+") (pintype "bidirectional"))
      (node (ref "R(ENTER)") (pin "B1") (pinfunction "2_B1") (pintype "passive"))
      (node (ref "R(ENTER)") (pin "B2") (pinfunction "2_B2") (pintype "passive"))
      (node (ref "R(ENTER)") (pin "B3") (pinfunction "2_B3") (pintype "passive"))
    )
    (net (code "72") (name "Net-(K(ESC)-P1)") (class "Default")
      (node (ref "D(ESC)") (pin "A1") (pinfunction "A_A1") (pintype "passive"))
      (node (ref "D(ESC)") (pin "A2") (pinfunction "A_A2") (pintype "passive"))
      (node (ref "D(ESC)") (pin "A3") (pinfunction "A_A3") (pintype "passive"))
      (node (ref "K(ESC)") (pin "MX2") (pinfunction "P1_MX2") (pintype "bidirectional"))
    )
    (net (code "73") (name "Net-(K(ESC)-PadLED+)") (class "Default")
      (node (ref "K(ESC)") (pin "LED+") (pinfunction "LED+_LED+") (pintype "bidirectional"))
      (node (ref "R(ESC)") (pin "B1") (pinfunction "2_B1") (pintype "passive"))
      (node (ref "R(ESC)") (pin "B2") (pinfunction "2_B2") (pintype "passive"))
      (node (ref "R(ESC)") (pin "B3") (pinfunction "2_B3") (pintype "passive"))
    )
    (net (code "74") (name "Net-(K(F)-P1)") (class "Default")
      (node (ref "D(F)") (pin "A1") (pinfunction "A_A1") (pintype "passive"))
      (node (ref "D(F)") (pin "A2") (pinfunction "A_A2") (pintype "passive"))
      (node (ref "D(F)") (pin "A3") (pinfunction "A_A3") (pintype "passive"))
      (node (ref "K(F)") (pin "MX2") (pinfunction "P1_MX2") (pintype "bidirectional"))
    )
    (net (code "75") (name "Net-(K(F)-PadLED+)") (class "Default")
      (node (ref "K(F)") (pin "LED+") (pinfunction "LED+_LED+") (pintype "bidirectional"))
      (node (ref "R(F)") (pin "B1") (pinfunction "2_B1") (pintype "passive"))
      (node (ref "R(F)") (pin "B2") (pinfunction "2_B2") (pintype "passive"))
      (node (ref "R(F)") (pin "B3") (pinfunction "2_B3") (pintype "passive"))
    )
    (net (code "76") (name "Net-(K(FN)-P1)") (class "Default")
      (node (ref "D(FN)") (pin "A1") (pinfunction "A_A1") (pintype "passive"))
      (node (ref "D(FN)") (pin "A2") (pinfunction "A_A2") (pintype "passive"))
      (node (ref "D(FN)") (pin "A3") (pinfunction "A_A3") (pintype "passive"))
      (node (ref "K(FN)") (pin "MX2") (pinfunction "P1_MX2") (pintype "bidirectional"))
    )
    (net (code "77") (name "Net-(K(FN)-PadLED+)") (class "Default")
      (node (ref "K(FN)") (pin "LED+") (pinfunction "LED+_LED+") (pintype "bidirectional"))
      (node (ref "R(FN)") (pin "B1") (pinfunction "2_B1") (pintype "passive"))
      (node (ref "R(FN)") (pin "B2") (pinfunction "2_B2") (pintype "passive"))
      (node (ref "R(FN)") (pin "B3") (pinfunction "2_B3") (pintype "passive"))
    )
    (net (code "78") (name "Net-(K(G)-P1)") (class "Default")
      (node (ref "D(G)") (pin "A1") (pinfunction "A_A1") (pintype "passive"))
      (node (ref "D(G)") (pin "A2") (pinfunction "A_A2") (pintype "passive"))
      (node (ref "D(G)") (pin "A3") (pinfunction "A_A3") (pintype "passive"))
      (node (ref "K(G)") (pin "MX2") (pinfunction "P1_MX2") (pintype "bidirectional"))
    )
    (net (code "79") (name "Net-(K(G)-PadLED+)") (class "Default")
      (node (ref "K(G)") (pin "LED+") (pinfunction "LED+_LED+") (pintype "bidirectional"))
      (node (ref "R(G)") (pin "B1") (pinfunction "2_B1") (pintype "passive"))
      (node (ref "R(G)") (pin "B2") (pinfunction "2_B2") (pintype "passive"))
      (node (ref "R(G)") (pin "B3") (pinfunction "2_B3") (pintype "passive"))
    )
    (net (code "80") (name "Net-(K(H)-P1)") (class "Default")
      (node (ref "D(H)") (pin "A1") (pinfunction "A_A1") (pintype "passive"))
      (node (ref "D(H)") (pin "A2") (pinfunction "A_A2") (pintype "passive"))
      (node (ref "D(H)") (pin "A3") (pinfunction "A_A3") (pintype "passive"))
      (node (ref "K(H)") (pin "MX2") (pinfunction "P1_MX2") (pintype "bidirectional"))
    )
    (net (code "81") (name "Net-(K(H)-PadLED+)") (class "Default")
      (node (ref "K(H)") (pin "LED+") (pinfunction "LED+_LED+") (pintype "bidirectional"))
      (node (ref "R(H)") (pin "B1") (pinfunction "2_B1") (pintype "passive"))
      (node (ref "R(H)") (pin "B2") (pinfunction "2_B2") (pintype "passive"))
      (node (ref "R(H)") (pin "B3") (pinfunction "2_B3") (pintype "passive"))
    )
    (net (code "82") (name "Net-(K(I)-P1)") (class "Default")
      (node (ref "D(I)") (pin "A1") (pinfunction "A_A1") (pintype "passive"))
      (node (ref "D(I)") (pin "A2") (pinfunction "A_A2") (pintype "passive"))
      (node (ref "D(I)") (pin "A3") (pinfunction "A_A3") (pintype "passive"))
      (node (ref "K(I)") (pin "MX2") (pinfunction "P1_MX2") (pintype "bidirectional"))
    )
    (net (code "83") (name "Net-(K(I)-PadLED+)") (class "Default")
      (node (ref "K(I)") (pin "LED+") (pinfunction "LED+_LED+") (pintype "bidirectional"))
      (node (ref "R(I)") (pin "B1") (pinfunction "2_B1") (pintype "passive"))
      (node (ref "R(I)") (pin "B2") (pinfunction "2_B2") (pintype "passive"))
      (node (ref "R(I)") (pin "B3") (pinfunction "2_B3") (pintype "passive"))
    )
    (net (code "84") (name "Net-(K(J)-P1)") (class "Default")
      (node (ref "D(J)") (pin "A1") (pinfunction "A_A1") (pintype "passive"))
      (node (ref "D(J)") (pin "A2") (pinfunction "A_A2") (pintype "passive"))
      (node (ref "D(J)") (pin "A3") (pinfunction "A_A3") (pintype "passive"))
      (node (ref "K(J)") (pin "MX2") (pinfunction "P1_MX2") (pintype "bidirectional"))
    )
    (net (code "85") (name "Net-(K(J)-PadLED+)") (class "Default")
      (node (ref "K(J)") (pin "LED+") (pinfunction "LED+_LED+") (pintype "bidirectional"))
      (node (ref "R(J)") (pin "B1") (pinfunction "2_B1") (pintype "passive"))
      (node (ref "R(J)") (pin "B2") (pinfunction "2_B2") (pintype "passive"))
      (node (ref "R(J)") (pin "B3") (pinfunction "2_B3") (pintype "passive"))
    )
    (net (code "86") (name "Net-(K(K)-P1)") (class "Default")
      (node (ref "D(K)") (pin "A1") (pinfunction "A_A1") (pintype "passive"))
      (node (ref "D(K)") (pin "A2") (pinfunction "A_A2") (pintype "passive"))
      (node (ref "D(K)") (pin "A3") (pinfunction "A_A3") (pintype "passive"))
      (node (ref "K(K)") (pin "MX2") (pinfunction "P1_MX2") (pintype "bidirectional"))
    )
    (net (code "87") (name "Net-(K(K)-PadLED+)") (class "Default")
      (node (ref "K(K)") (pin "LED+") (pinfunction "LED+_LED+") (pintype "bidirectional"))
      (node (ref "R(K)") (pin "B1") (pinfunction "2_B1") (pintype "passive"))
      (node (ref "R(K)") (pin "B2") (pinfunction "2_B2") (pintype "passive"))
      (node (ref "R(K)") (pin "B3") (pinfunction "2_B3") (pintype "passive"))
    )
    (net (code "88") (name "Net-(K(L)-P1)") (class "Default")
      (node (ref "D(L)") (pin "A1") (pinfunction "A_A1") (pintype "passive"))
      (node (ref "D(L)") (pin "A2") (pinfunction "A_A2") (pintype "passive"))
      (node (ref "D(L)") (pin "A3") (pinfunction "A_A3") (pintype "passive"))
      (node (ref "K(L)") (pin "MX2") (pinfunction "P1_MX2") (pintype "bidirectional"))
    )
    (net (code "89") (name "Net-(K(L)-PadLED+)") (class "Default")
      (node (ref "K(L)") (pin "LED+") (pinfunction "LED+_LED+") (pintype "bidirectional"))
      (node (ref "R(L)") (pin "B1") (pinfunction "2_B1") (pintype "passive"))
      (node (ref "R(L)") (pin "B2") (pinfunction "2_B2") (pintype "passive"))
      (node (ref "R(L)") (pin "B3") (pinfunction "2_B3") (pintype "passive"))
    )
    (net (code "90") (name "Net-(K(LALT)-P1)") (class "Default")
      (node (ref "D(LALT)") (pin "A1") (pinfunction "A_A1") (pintype "passive"))
      (node (ref "D(LALT)") (pin "A2") (pinfunction "A_A2") (pintype "passive"))
      (node (ref "D(LALT)") (pin "A3") (pinfunction "A_A3") (pintype "passive"))
      (node (ref "K(LALT)") (pin "MX2") (pinfunction "P1_MX2") (pintype "bidirectional"))
    )
    (net (code "91") (name "Net-(K(LALT)-PadLED+)") (class "Default")
      (node (ref "K(LALT)") (pin "LED+") (pinfunction "LED+_LED+") (pintype "bidirectional"))
      (node (ref "R(LALT)") (pin "A1") (pinfunction "1_A1") (pintype "passive"))
      (node (ref "R(LALT)") (pin "A2") (pinfunction "1_A2") (pintype "passive"))
      (node (ref "R(LALT)") (pin "A3") (pinfunction "1_A3") (pintype "passive"))
    )
    (net (code "92") (name "Net-(K(LCTRL)-P1)") (class "Default")
      (node (ref "D(LCTRL)") (pin "A1") (pinfunction "A_A1") (pintype "passive"))
      (node (ref "D(LCTRL)") (pin "A2") (pinfunction "A_A2") (pintype "passive"))
      (node (ref "D(LCTRL)") (pin "A3") (pinfunction "A_A3") (pintype "passive"))
      (node (ref "K(LCTRL)") (pin "MX2") (pinfunction "P1_MX2") (pintype "bidirectional"))
    )
    (net (code "93") (name "Net-(K(LCTRL)-PadLED+)") (class "Default")
      (node (ref "K(LCTRL)") (pin "LED+") (pinfunction "LED+_LED+") (pintype "bidirectional"))
      (node (ref "R(LCTRL)") (pin "A1") (pinfunction "1_A1") (pintype "passive"))
      (node (ref "R(LCTRL)") (pin "A2") (pinfunction "1_A2") (pintype "passive"))
      (node (ref "R(LCTRL)") (pin "A3") (pinfunction "1_A3") (pintype "passive"))
    )
    (net (code "94") (name "Net-(K(LSHIFT)-P1)") (class "Default")
      (node (ref "D(LSHIFT)") (pin "A1") (pinfunction "A_A1") (pintype "passive"))
      (node (ref "D(LSHIFT)") (pin "A2") (pinfunction "A_A2") (pintype "passive"))
      (node (ref "D(LSHIFT)") (pin "A3") (pinfunction "A_A3") (pintype "passive"))
      (node (ref "K(LSHIFT)") (pin "MX2") (pinfunction "P1_MX2") (pintype "bidirectional"))
    )
    (net (code "95") (name "Net-(K(LSHIFT)-PadLED+)") (class "Default")
      (node (ref "K(LSHIFT)") (pin "LED+") (pinfunction "LED+_LED+") (pintype "bidirectional"))
      (node (ref "R(LSHIFT)") (pin "B1") (pinfunction "2_B1") (pintype "passive"))
      (node (ref "R(LSHIFT)") (pin "B2") (pinfunction "2_B2") (pintype "passive"))
      (node (ref "R(LSHIFT)") (pin "B3") (pinfunction "2_B3") (pintype "passive"))
    )
    (net (code "96") (name "Net-(K(LSUPER)-P1)") (class "Default")
      (node (ref "D(LSUPER)") (pin "A1") (pinfunction "A_A1") (pintype "passive"))
      (node (ref "D(LSUPER)") (pin "A2") (pinfunction "A_A2") (pintype "passive"))
      (node (ref "D(LSUPER)") (pin "A3") (pinfunction "A_A3") (pintype "passive"))
      (node (ref "K(LSUPER)") (pin "MX2") (pinfunction "P1_MX2") (pintype "bidirectional"))
    )
    (net (code "97") (name "Net-(K(LSUPER)-PadLED+)") (class "Default")
      (node (ref "K(LSUPER)") (pin "LED+") (pinfunction "LED+_LED+") (pintype "bidirectional"))
      (node (ref "L(LSUPER)") (pin "A1") (pinfunction "1_A1") (pintype "passive"))
      (node (ref "L(LSUPER)") (pin "A2") (pinfunction "1_A2") (pintype "passive"))
      (node (ref "L(LSUPER)") (pin "A3") (pinfunction "1_A3") (pintype "passive"))
    )
    (net (code "98") (name "Net-(K(M)-P1)") (class "Default")
      (node (ref "D(M)") (pin "A1") (pinfunction "A_A1") (pintype "passive"))
      (node (ref "D(M)") (pin "A2") (pinfunction "A_A2") (pintype "passive"))
      (node (ref "D(M)") (pin "A3") (pinfunction "A_A3") (pintype "passive"))
      (node (ref "K(M)") (pin "MX2") (pinfunction "P1_MX2") (pintype "bidirectional"))
    )
    (net (code "99") (name "Net-(K(M)-PadLED+)") (class "Default")
      (node (ref "K(M)") (pin "LED+") (pinfunction "LED+_LED+") (pintype "bidirectional"))
      (node (ref "R(M)") (pin "B1") (pinfunction "2_B1") (pintype "passive"))
      (node (ref "R(M)") (pin "B2") (pinfunction "2_B2") (pintype "passive"))
      (node (ref "R(M)") (pin "B3") (pinfunction "2_B3") (pintype "passive"))
    )
    (net (code "100") (name "Net-(K(N)-P1)") (class "Default")
      (node (ref "D(N)") (pin "A1") (pinfunction "A_A1") (pintype "passive"))
      (node (ref "D(N)") (pin "A2") (pinfunction "A_A2") (pintype "passive"))
      (node (ref "D(N)") (pin "A3") (pinfunction "A_A3") (pintype "passive"))
      (node (ref "K(N)") (pin "MX2") (pinfunction "P1_MX2") (pintype "bidirectional"))
    )
    (net (code "101") (name "Net-(K(N)-PadLED+)") (class "Default")
      (node (ref "K(N)") (pin "LED+") (pinfunction "LED+_LED+") (pintype "bidirectional"))
      (node (ref "R(N)") (pin "B1") (pinfunction "2_B1") (pintype "passive"))
      (node (ref "R(N)") (pin "B2") (pinfunction "2_B2") (pintype "passive"))
      (node (ref "R(N)") (pin "B3") (pinfunction "2_B3") (pintype "passive"))
    )
    (net (code "102") (name "Net-(K(O)-LED+)") (class "Default")
      (node (ref "K(O)") (pin "SMDLED+") (pinfunction "LED+_SMDLED+") (pintype "bidirectional"))
      (node (ref "R(O)") (pin "B1") (pinfunction "2_B1") (pintype "passive"))
      (node (ref "R(O)") (pin "B2") (pinfunction "2_B2") (pintype "passive"))
      (node (ref "R(O)") (pin "B3") (pinfunction "2_B3") (pintype "passive"))
    )
    (net (code "103") (name "Net-(K(O)-P1)") (class "Default")
      (node (ref "D(O)") (pin "A1") (pinfunction "A_A1") (pintype "passive"))
      (node (ref "D(O)") (pin "A2") (pinfunction "A_A2") (pintype "passive"))
      (node (ref "D(O)") (pin "A3") (pinfunction "A_A3") (pintype "passive"))
      (node (ref "K(O)") (pin "MX2") (pinfunction "P1_MX2") (pintype "bidirectional"))
    )
    (net (code "104") (name "Net-(K(P)-P1)") (class "Default")
      (node (ref "D(P)") (pin "A1") (pinfunction "A_A1") (pintype "passive"))
      (node (ref "D(P)") (pin "A2") (pinfunction "A_A2") (pintype "passive"))
      (node (ref "D(P)") (pin "A3") (pinfunction "A_A3") (pintype "passive"))
      (node (ref "K(P)") (pin "MX2") (pinfunction "P1_MX2") (pintype "bidirectional"))
    )
    (net (code "105") (name "Net-(K(P)-PadLED+)") (class "Default")
      (node (ref "K(P)") (pin "LED+") (pinfunction "LED+_LED+") (pintype "bidirectional"))
      (node (ref "R(P)") (pin "B1") (pinfunction "2_B1") (pintype "passive"))
      (node (ref "R(P)") (pin "B2") (pinfunction "2_B2") (pintype "passive"))
      (node (ref "R(P)") (pin "B3") (pinfunction "2_B3") (pintype "passive"))
    )
    (net (code "106") (name "Net-(K(Q)-P1)") (class "Default")
      (node (ref "D(Q)") (pin "A1") (pinfunction "A_A1") (pintype "passive"))
      (node (ref "D(Q)") (pin "A2") (pinfunction "A_A2") (pintype "passive"))
      (node (ref "D(Q)") (pin "A3") (pinfunction "A_A3") (pintype "passive"))
      (node (ref "K(Q)") (pin "MX2") (pinfunction "P1_MX2") (pintype "bidirectional"))
    )
    (net (code "107") (name "Net-(K(Q)-PadLED+)") (class "Default")
      (node (ref "K(Q)") (pin "LED+") (pinfunction "LED+_LED+") (pintype "bidirectional"))
      (node (ref "R(Q)") (pin "B1") (pinfunction "2_B1") (pintype "passive"))
      (node (ref "R(Q)") (pin "B2") (pinfunction "2_B2") (pintype "passive"))
      (node (ref "R(Q)") (pin "B3") (pinfunction "2_B3") (pintype "passive"))
    )
    (net (code "108") (name "Net-(K(QUOTE)-P1)") (class "Default")
      (node (ref "D(QUOTE)") (pin "A1") (pinfunction "A_A1") (pintype "passive"))
      (node (ref "D(QUOTE)") (pin "A2") (pinfunction "A_A2") (pintype "passive"))
      (node (ref "D(QUOTE)") (pin "A3") (pinfunction "A_A3") (pintype "passive"))
      (node (ref "K(QUOTE)") (pin "MX2") (pinfunction "P1_MX2") (pintype "bidirectional"))
    )
    (net (code "109") (name "Net-(K(QUOTE)-PadLED+)") (class "Default")
      (node (ref "K(QUOTE)") (pin "LED+") (pinfunction "LED+_LED+") (pintype "bidirectional"))
      (node (ref "R(QUOTE)") (pin "B1") (pinfunction "2_B1") (pintype "passive"))
      (node (ref "R(QUOTE)") (pin "B2") (pinfunction "2_B2") (pintype "passive"))
      (node (ref "R(QUOTE)") (pin "B3") (pinfunction "2_B3") (pintype "passive"))
    )
    (net (code "110") (name "Net-(K(R)-P1)") (class "Default")
      (node (ref "D(R)") (pin "A1") (pinfunction "A_A1") (pintype "passive"))
      (node (ref "D(R)") (pin "A2") (pinfunction "A_A2") (pintype "passive"))
      (node (ref "D(R)") (pin "A3") (pinfunction "A_A3") (pintype "passive"))
      (node (ref "K(R)") (pin "MX2") (pinfunction "P1_MX2") (pintype "bidirectional"))
    )
    (net (code "111") (name "Net-(K(R)-PadLED+)") (class "Default")
      (node (ref "K(R)") (pin "LED+") (pinfunction "LED+_LED+") (pintype "bidirectional"))
      (node (ref "R(R)") (pin "B1") (pinfunction "2_B1") (pintype "passive"))
      (node (ref "R(R)") (pin "B2") (pinfunction "2_B2") (pintype "passive"))
      (node (ref "R(R)") (pin "B3") (pinfunction "2_B3") (pintype "passive"))
    )
    (net (code "112") (name "Net-(K(RALT)-P1)") (class "Default")
      (node (ref "D(RALT)") (pin "A1") (pinfunction "A_A1") (pintype "passive"))
      (node (ref "D(RALT)") (pin "A2") (pinfunction "A_A2") (pintype "passive"))
      (node (ref "D(RALT)") (pin "A3") (pinfunction "A_A3") (pintype "passive"))
      (node (ref "K(RALT)") (pin "MX2") (pinfunction "P1_MX2") (pintype "bidirectional"))
    )
    (net (code "113") (name "Net-(K(RALT)-PadLED+)") (class "Default")
      (node (ref "K(RALT)") (pin "LED+") (pinfunction "LED+_LED+") (pintype "bidirectional"))
      (node (ref "R(RALT)") (pin "B1") (pinfunction "2_B1") (pintype "passive"))
      (node (ref "R(RALT)") (pin "B2") (pinfunction "2_B2") (pintype "passive"))
      (node (ref "R(RALT)") (pin "B3") (pinfunction "2_B3") (pintype "passive"))
    )
    (net (code "114") (name "Net-(K(RCTRL)-P1)") (class "Default")
      (node (ref "D(RCTRL)") (pin "A1") (pinfunction "A_A1") (pintype "passive"))
      (node (ref "D(RCTRL)") (pin "A2") (pinfunction "A_A2") (pintype "passive"))
      (node (ref "D(RCTRL)") (pin "A3") (pinfunction "A_A3") (pintype "passive"))
      (node (ref "K(RCTRL)") (pin "MX2") (pinfunction "P1_MX2") (pintype "bidirectional"))
    )
    (net (code "115") (name "Net-(K(RCTRL)-PadLED+)") (class "Default")
      (node (ref "K(RCTRL)") (pin "LED+") (pinfunction "LED+_LED+") (pintype "bidirectional"))
      (node (ref "R(RCTRL)") (pin "B1") (pinfunction "2_B1") (pintype "passive"))
      (node (ref "R(RCTRL)") (pin "B2") (pinfunction "2_B2") (pintype "passive"))
      (node (ref "R(RCTRL)") (pin "B3") (pinfunction "2_B3") (pintype "passive"))
    )
    (net (code "116") (name "Net-(K(RSHIFT)-P1)") (class "Default")
      (node (ref "D(RSHIFT)") (pin "A1") (pinfunction "A_A1") (pintype "passive"))
      (node (ref "D(RSHIFT)") (pin "A2") (pinfunction "A_A2") (pintype "passive"))
      (node (ref "D(RSHIFT)") (pin "A3") (pinfunction "A_A3") (pintype "passive"))
      (node (ref "K(RSHIFT)") (pin "MX2") (pinfunction "P1_MX2") (pintype "bidirectional"))
    )
    (net (code "117") (name "Net-(K(RSHIFT)-PadLED+)") (class "Default")
      (node (ref "K(RSHIFT)") (pin "LED+") (pinfunction "LED+_LED+") (pintype "bidirectional"))
      (node (ref "R(RSHIFT)") (pin "B1") (pinfunction "2_B1") (pintype "passive"))
      (node (ref "R(RSHIFT)") (pin "B2") (pinfunction "2_B2") (pintype "passive"))
      (node (ref "R(RSHIFT)") (pin "B3") (pinfunction "2_B3") (pintype "passive"))
    )
    (net (code "118") (name "Net-(K(RSUPER)-P1)") (class "Default")
      (node (ref "D(RSUPER)") (pin "A1") (pinfunction "A_A1") (pintype "passive"))
      (node (ref "D(RSUPER)") (pin "A2") (pinfunction "A_A2") (pintype "passive"))
      (node (ref "D(RSUPER)") (pin "A3") (pinfunction "A_A3") (pintype "passive"))
      (node (ref "K(RSUPER)") (pin "MX2") (pinfunction "P1_MX2") (pintype "bidirectional"))
    )
    (net (code "119") (name "Net-(K(RSUPER)-PadLED+)") (class "Default")
      (node (ref "K(RSUPER)") (pin "LED+") (pinfunction "LED+_LED+") (pintype "bidirectional"))
      (node (ref "R(RSUPER)") (pin "B1") (pinfunction "2_B1") (pintype "passive"))
      (node (ref "R(RSUPER)") (pin "B2") (pinfunction "2_B2") (pintype "passive"))
      (node (ref "R(RSUPER)") (pin "B3") (pinfunction "2_B3") (pintype "passive"))
    )
    (net (code "120") (name "Net-(K(S)-P1)") (class "Default")
      (node (ref "D(S)") (pin "A1") (pinfunction "A_A1") (pintype "passive"))
      (node (ref "D(S)") (pin "A2") (pinfunction "A_A2") (pintype "passive"))
      (node (ref "D(S)") (pin "A3") (pinfunction "A_A3") (pintype "passive"))
      (node (ref "K(S)") (pin "MX2") (pinfunction "P1_MX2") (pintype "bidirectional"))
    )
    (net (code "121") (name "Net-(K(S)-PadLED+)") (class "Default")
      (node (ref "K(S)") (pin "LED+") (pinfunction "LED+_LED+") (pintype "bidirectional"))
      (node (ref "R(S)") (pin "B1") (pinfunction "2_B1") (pintype "passive"))
      (node (ref "R(S)") (pin "B2") (pinfunction "2_B2") (pintype "passive"))
      (node (ref "R(S)") (pin "B3") (pinfunction "2_B3") (pintype "passive"))
    )
    (net (code "122") (name "Net-(K(SPC)-P1)") (class "Default")
      (node (ref "D(SPC)") (pin "A1") (pinfunction "A_A1") (pintype "passive"))
      (node (ref "D(SPC)") (pin "A2") (pinfunction "A_A2") (pintype "passive"))
      (node (ref "D(SPC)") (pin "A3") (pinfunction "A_A3") (pintype "passive"))
      (node (ref "K(SPC)") (pin "MX2") (pinfunction "P1_MX2") (pintype "bidirectional"))
    )
    (net (code "123") (name "Net-(K(SPC)-PadLED+)") (class "Default")
      (node (ref "K(SPC)") (pin "LED+") (pinfunction "LED+_LED+") (pintype "bidirectional"))
      (node (ref "R(SPC)") (pin "B1") (pinfunction "2_B1") (pintype "passive"))
      (node (ref "R(SPC)") (pin "B2") (pinfunction "2_B2") (pintype "passive"))
      (node (ref "R(SPC)") (pin "B3") (pinfunction "2_B3") (pintype "passive"))
    )
    (net (code "124") (name "Net-(K(T)-P1)") (class "Default")
      (node (ref "D(T)") (pin "A1") (pinfunction "A_A1") (pintype "passive"))
      (node (ref "D(T)") (pin "A2") (pinfunction "A_A2") (pintype "passive"))
      (node (ref "D(T)") (pin "A3") (pinfunction "A_A3") (pintype "passive"))
      (node (ref "K(T)") (pin "MX2") (pinfunction "P1_MX2") (pintype "bidirectional"))
    )
    (net (code "125") (name "Net-(K(T)-PadLED+)") (class "Default")
      (node (ref "K(T)") (pin "LED+") (pinfunction "LED+_LED+") (pintype "bidirectional"))
      (node (ref "R(T)") (pin "B1") (pinfunction "2_B1") (pintype "passive"))
      (node (ref "R(T)") (pin "B2") (pinfunction "2_B2") (pintype "passive"))
      (node (ref "R(T)") (pin "B3") (pinfunction "2_B3") (pintype "passive"))
    )
    (net (code "126") (name "Net-(K(TAB)-P1)") (class "Default")
      (node (ref "D(TAB)") (pin "A1") (pinfunction "A_A1") (pintype "passive"))
      (node (ref "D(TAB)") (pin "A2") (pinfunction "A_A2") (pintype "passive"))
      (node (ref "D(TAB)") (pin "A3") (pinfunction "A_A3") (pintype "passive"))
      (node (ref "K(TAB)") (pin "MX2") (pinfunction "P1_MX2") (pintype "bidirectional"))
    )
    (net (code "127") (name "Net-(K(TAB)-PadLED+)") (class "Default")
      (node (ref "K(TAB)") (pin "LED+") (pinfunction "LED+_LED+") (pintype "bidirectional"))
      (node (ref "R(TAB)") (pin "B1") (pinfunction "2_B1") (pintype "passive"))
      (node (ref "R(TAB)") (pin "B2") (pinfunction "2_B2") (pintype "passive"))
      (node (ref "R(TAB)") (pin "B3") (pinfunction "2_B3") (pintype "passive"))
    )
    (net (code "128") (name "Net-(K(U)-P1)") (class "Default")
      (node (ref "D(U)") (pin "A1") (pinfunction "A_A1") (pintype "passive"))
      (node (ref "D(U)") (pin "A2") (pinfunction "A_A2") (pintype "passive"))
      (node (ref "D(U)") (pin "A3") (pinfunction "A_A3") (pintype "passive"))
      (node (ref "K(U)") (pin "MX2") (pinfunction "P1_MX2") (pintype "bidirectional"))
    )
    (net (code "129") (name "Net-(K(U)-PadLED+)") (class "Default")
      (node (ref "K(U)") (pin "LED+") (pinfunction "LED+_LED+") (pintype "bidirectional"))
      (node (ref "R(U)") (pin "B1") (pinfunction "2_B1") (pintype "passive"))
      (node (ref "R(U)") (pin "B2") (pinfunction "2_B2") (pintype "passive"))
      (node (ref "R(U)") (pin "B3") (pinfunction "2_B3") (pintype "passive"))
    )
    (net (code "130") (name "Net-(K(V)-P1)") (class "Default")
      (node (ref "D(V)") (pin "A1") (pinfunction "A_A1") (pintype "passive"))
      (node (ref "D(V)") (pin "A2") (pinfunction "A_A2") (pintype "passive"))
      (node (ref "D(V)") (pin "A3") (pinfunction "A_A3") (pintype "passive"))
      (node (ref "K(V)") (pin "MX2") (pinfunction "P1_MX2") (pintype "bidirectional"))
    )
    (net (code "131") (name "Net-(K(V)-PadLED+)") (class "Default")
      (node (ref "K(V)") (pin "LED+") (pinfunction "LED+_LED+") (pintype "bidirectional"))
      (node (ref "R(V)") (pin "B1") (pinfunction "2_B1") (pintype "passive"))
      (node (ref "R(V)") (pin "B2") (pinfunction "2_B2") (pintype "passive"))
      (node (ref "R(V)") (pin "B3") (pinfunction "2_B3") (pintype "passive"))
    )
    (net (code "132") (name "Net-(K(W)-P1)") (class "Default")
      (node (ref "D(W)") (pin "A1") (pinfunction "A_A1") (pintype "passive"))
      (node (ref "D(W)") (pin "A2") (pinfunction "A_A2") (pintype "passive"))
      (node (ref "D(W)") (pin "A3") (pinfunction "A_A3") (pintype "passive"))
      (node (ref "K(W)") (pin "MX2") (pinfunction "P1_MX2") (pintype "bidirectional"))
    )
    (net (code "133") (name "Net-(K(W)-PadLED+)") (class "Default")
      (node (ref "K(W)") (pin "LED+") (pinfunction "LED+_LED+") (pintype "bidirectional"))
      (node (ref "R(W)") (pin "B1") (pinfunction "2_B1") (pintype "passive"))
      (node (ref "R(W)") (pin "B2") (pinfunction "2_B2") (pintype "passive"))
      (node (ref "R(W)") (pin "B3") (pinfunction "2_B3") (pintype "passive"))
    )
    (net (code "134") (name "Net-(K(X)-P1)") (class "Default")
      (node (ref "D(X)") (pin "A1") (pinfunction "A_A1") (pintype "passive"))
      (node (ref "D(X)") (pin "A2") (pinfunction "A_A2") (pintype "passive"))
      (node (ref "D(X)") (pin "A3") (pinfunction "A_A3") (pintype "passive"))
      (node (ref "K(X)") (pin "MX2") (pinfunction "P1_MX2") (pintype "bidirectional"))
    )
    (net (code "135") (name "Net-(K(X)-PadLED+)") (class "Default")
      (node (ref "K(X)") (pin "LED+") (pinfunction "LED+_LED+") (pintype "bidirectional"))
      (node (ref "R(X)") (pin "B1") (pinfunction "2_B1") (pintype "passive"))
      (node (ref "R(X)") (pin "B2") (pinfunction "2_B2") (pintype "passive"))
      (node (ref "R(X)") (pin "B3") (pinfunction "2_B3") (pintype "passive"))
    )
    (net (code "136") (name "Net-(K(Y)-P1)") (class "Default")
      (node (ref "D(Y)") (pin "A1") (pinfunction "A_A1") (pintype "passive"))
      (node (ref "D(Y)") (pin "A2") (pinfunction "A_A2") (pintype "passive"))
      (node (ref "D(Y)") (pin "A3") (pinfunction "A_A3") (pintype "passive"))
      (node (ref "K(Y)") (pin "MX2") (pinfunction "P1_MX2") (pintype "bidirectional"))
    )
    (net (code "137") (name "Net-(K(Y)-PadLED+)") (class "Default")
      (node (ref "K(Y)") (pin "LED+") (pinfunction "LED+_LED+") (pintype "bidirectional"))
      (node (ref "R(Y)") (pin "B1") (pinfunction "2_B1") (pintype "passive"))
      (node (ref "R(Y)") (pin "B2") (pinfunction "2_B2") (pintype "passive"))
      (node (ref "R(Y)") (pin "B3") (pinfunction "2_B3") (pintype "passive"))
    )
    (net (code "138") (name "Net-(K(Z)-P1)") (class "Default")
      (node (ref "D(Z)") (pin "A1") (pinfunction "A_A1") (pintype "passive"))
      (node (ref "D(Z)") (pin "A2") (pinfunction "A_A2") (pintype "passive"))
      (node (ref "D(Z)") (pin "A3") (pinfunction "A_A3") (pintype "passive"))
      (node (ref "K(Z)") (pin "MX2") (pinfunction "P1_MX2") (pintype "bidirectional"))
    )
    (net (code "139") (name "Net-(K(Z)-PadLED+)") (class "Default")
      (node (ref "K(Z)") (pin "LED+") (pinfunction "LED+_LED+") (pintype "bidirectional"))
      (node (ref "R(Z)") (pin "B1") (pinfunction "2_B1") (pintype "passive"))
      (node (ref "R(Z)") (pin "B2") (pinfunction "2_B2") (pintype "passive"))
      (node (ref "R(Z)") (pin "B3") (pinfunction "2_B3") (pintype "passive"))
    )
    (net (code "140") (name "Net-(K([)-P1)") (class "Default")
      (node (ref "D([)") (pin "A1") (pinfunction "A_A1") (pintype "passive"))
      (node (ref "D([)") (pin "A2") (pinfunction "A_A2") (pintype "passive"))
      (node (ref "D([)") (pin "A3") (pinfunction "A_A3") (pintype "passive"))
      (node (ref "K([)") (pin "MX2") (pinfunction "P1_MX2") (pintype "bidirectional"))
    )
    (net (code "141") (name "Net-(K([)-PadLED+)") (class "Default")
      (node (ref "K([)") (pin "LED+") (pinfunction "LED+_LED+") (pintype "bidirectional"))
      (node (ref "R([)") (pin "B1") (pinfunction "2_B1") (pintype "passive"))
      (node (ref "R([)") (pin "B2") (pinfunction "2_B2") (pintype "passive"))
      (node (ref "R([)") (pin "B3") (pinfunction "2_B3") (pintype "passive"))
    )
    (net (code "142") (name "Net-(K(\\\\)-P1)") (class "Default")
      (node (ref "D(\\\\)") (pin "A1") (pinfunction "A_A1") (pintype "passive"))
      (node (ref "D(\\\\)") (pin "A2") (pinfunction "A_A2") (pintype "passive"))
      (node (ref "D(\\\\)") (pin "A3") (pinfunction "A_A3") (pintype "passive"))
      (node (ref "K(\\\\)") (pin "MX2") (pinfunction "P1_MX2") (pintype "bidirectional"))
    )
    (net (code "143") (name "Net-(K(\\\\)-PadLED+)") (class "Default")
      (node (ref "K(\\\\)") (pin "LED+") (pinfunction "LED+_LED+") (pintype "bidirectional"))
      (node (ref "R(\\\\)") (pin "B1") (pinfunction "2_B1") (pintype "passive"))
      (node (ref "R(\\\\)") (pin "B2") (pinfunction "2_B2") (pintype "passive"))
      (node (ref "R(\\\\)") (pin "B3") (pinfunction "2_B3") (pintype "passive"))
    )
    (net (code "144") (name "Net-(K(])-P1)") (class "Default")
      (node (ref "D(])") (pin "A1") (pinfunction "A_A1") (pintype "passive"))
      (node (ref "D(])") (pin "A2") (pinfunction "A_A2") (pintype "passive"))
      (node (ref "D(])") (pin "A3") (pinfunction "A_A3") (pintype "passive"))
      (node (ref "K(])") (pin "MX2") (pinfunction "P1_MX2") (pintype "bidirectional"))
    )
    (net (code "145") (name "Net-(K(])-PadLED+)") (class "Default")
      (node (ref "K(])") (pin "LED+") (pinfunction "LED+_LED+") (pintype "bidirectional"))
      (node (ref "R(])") (pin "B1") (pinfunction "2_B1") (pintype "passive"))
      (node (ref "R(])") (pin "B2") (pinfunction "2_B2") (pintype "passive"))
      (node (ref "R(])") (pin "B3") (pinfunction "2_B3") (pintype "passive"))
    )
    (net (code "146") (name "Net-(K(~)-P1)") (class "Default")
      (node (ref "D(~)") (pin "A1") (pinfunction "A_A1") (pintype "passive"))
      (node (ref "D(~)") (pin "A2") (pinfunction "A_A2") (pintype "passive"))
      (node (ref "D(~)") (pin "A3") (pinfunction "A_A3") (pintype "passive"))
      (node (ref "K(~)") (pin "MX2") (pinfunction "P1_MX2") (pintype "bidirectional"))
    )
    (net (code "147") (name "Net-(K(~)-PadLED+)") (class "Default")
      (node (ref "K(~)") (pin "LED+") (pinfunction "LED+_LED+") (pintype "bidirectional"))
      (node (ref "R(~)") (pin "B1") (pinfunction "2_B1") (pintype "passive"))
      (node (ref "R(~)") (pin "B2") (pinfunction "2_B2") (pintype "passive"))
      (node (ref "R(~)") (pin "B3") (pinfunction "2_B3") (pintype "passive"))
    )
    (net (code "148") (name "Net-(S1-S)") (class "Default")
      (node (ref "R3") (pin "2") (pinfunction "2_2") (pintype "passive"))
      (node (ref "S1") (pin "1") (pinfunction "S_1") (pintype "passive"))
      (node (ref "S1") (pin "2") (pinfunction "S1_2") (pintype "passive"))
      (node (ref "U$1") (pin "13") (pinfunction "~{RESET}_13") (pintype "bidirectional"))
    )
    (net (code "149") (name "Net-(U$1-D+)") (class "Default")
      (node (ref "R1") (pin "2") (pinfunction "2_2") (pintype "passive"))
      (node (ref "U$1") (pin "4") (pinfunction "D+_4") (pintype "bidirectional"))
    )
    (net (code "150") (name "Net-(U$1-D-)") (class "Default")
      (node (ref "R2") (pin "2") (pinfunction "2_2") (pintype "passive"))
      (node (ref "U$1") (pin "3") (pinfunction "D-_3") (pintype "bidirectional"))
    )
    (net (code "151") (name "Net-(U$1-PE2{slash}~{HWB})") (class "Default")
      (node (ref "R4") (pin "2") (pinfunction "2_2") (pintype "passive"))
      (node (ref "U$1") (pin "33") (pinfunction "PE2/~{HWB}_33") (pintype "bidirectional"))
    )
    (net (code "152") (name "Net-(U$1-UCAP)") (class "Default")
      (node (ref "C3") (pin "1") (pinfunction "1_1") (pintype "passive"))
      (node (ref "U$1") (pin "6") (pinfunction "UCAP_6") (pintype "bidirectional"))
    )
    (net (code "153") (name "Net-(U$1-XTAL1)") (class "Default")
      (node (ref "C1") (pin "1") (pinfunction "1_1") (pintype "passive"))
      (node (ref "Q1") (pin "2") (pinfunction "2_2") (pintype "passive"))
      (node (ref "U$1") (pin "17") (pinfunction "XTAL1_17") (pintype "bidirectional"))
    )
    (net (code "154") (name "Net-(U$1-XTAL2)") (class "Default")
      (node (ref "C2") (pin "1") (pinfunction "1_1") (pintype "passive"))
      (node (ref "Q1") (pin "1") (pinfunction "1_1") (pintype "passive"))
      (node (ref "U$1") (pin "16") (pinfunction "XTAL2_16") (pintype "bidirectional"))
    )
    (net (code "155") (name "P42") (class "Default")
      (node (ref "U$1") (pin "42") (pinfunction "AREF_42") (pintype "bidirectional"))
    )
    (net (code "156") (name "ROW1") (class "Default")
      (node (ref "D(+)") (pin "C1") (pinfunction "C_C1") (pintype "passive"))
      (node (ref "D(+)") (pin "C2") (pinfunction "C_C2") (pintype "passive"))
      (node (ref "D(+)") (pin "C3") (pinfunction "C_C3") (pintype "passive"))
      (node (ref "D(-)") (pin "C1") (pinfunction "C_C1") (pintype "passive"))
      (node (ref "D(-)") (pin "C2") (pinfunction "C_C2") (pintype "passive"))
      (node (ref "D(-)") (pin "C3") (pinfunction "C_C3") (pintype "passive"))
      (node (ref "D(0)") (pin "C1") (pinfunction "C_C1") (pintype "passive"))
      (node (ref "D(0)") (pin "C2") (pinfunction "C_C2") (pintype "passive"))
      (node (ref "D(0)") (pin "C3") (pinfunction "C_C3") (pintype "passive"))
      (node (ref "D(1)") (pin "C1") (pinfunction "C_C1") (pintype "passive"))
      (node (ref "D(1)") (pin "C2") (pinfunction "C_C2") (pintype "passive"))
      (node (ref "D(1)") (pin "C3") (pinfunction "C_C3") (pintype "passive"))
      (node (ref "D(2)") (pin "C1") (pinfunction "C_C1") (pintype "passive"))
      (node (ref "D(2)") (pin "C2") (pinfunction "C_C2") (pintype "passive"))
      (node (ref "D(2)") (pin "C3") (pinfunction "C_C3") (pintype "passive"))
      (node (ref "D(3)") (pin "C1") (pinfunction "C_C1") (pintype "passive"))
      (node (ref "D(3)") (pin "C2") (pinfunction "C_C2") (pintype "passive"))
      (node (ref "D(3)") (pin "C3") (pinfunction "C_C3") (pintype "passive"))
      (node (ref "D(4)") (pin "C1") (pinfunction "C_C1") (pintype "passive"))
      (node (ref "D(4)") (pin "C2") (pinfunction "C_C2") (pintype "passive"))
      (node (ref "D(4)") (pin "C3") (pinfunction "C_C3") (pintype "passive"))
      (node (ref "D(5)") (pin "C1") (pinfunction "C_C1") (pintype "passive"))
      (node (ref "D(5)") (pin "C2") (pinfunction "C_C2") (pintype "passive"))
      (node (ref "D(5)") (pin "C3") (pinfunction "C_C3") (pintype "passive"))
      (node (ref "D(6)") (pin "C1") (pinfunction "C_C1") (pintype "passive"))
      (node (ref "D(6)") (pin "C2") (pinfunction "C_C2") (pintype "passive"))
      (node (ref "D(6)") (pin "C3") (pinfunction "C_C3") (pintype "passive"))
      (node (ref "D(7)") (pin "C1") (pinfunction "C_C1") (pintype "passive"))
      (node (ref "D(7)") (pin "C2") (pinfunction "C_C2") (pintype "passive"))
      (node (ref "D(7)") (pin "C3") (pinfunction "C_C3") (pintype "passive"))
      (node (ref "D(8)") (pin "C1") (pinfunction "C_C1") (pintype "passive"))
      (node (ref "D(8)") (pin "C2") (pinfunction "C_C2") (pintype "passive"))
      (node (ref "D(8)") (pin "C3") (pinfunction "C_C3") (pintype "passive"))
      (node (ref "D(9)") (pin "C1") (pinfunction "C_C1") (pintype "passive"))
      (node (ref "D(9)") (pin "C2") (pinfunction "C_C2") (pintype "passive"))
      (node (ref "D(9)") (pin "C3") (pinfunction "C_C3") (pintype "passive"))
      (node (ref "D(ESC)") (pin "C1") (pinfunction "C_C1") (pintype "passive"))
      (node (ref "D(ESC)") (pin "C2") (pinfunction "C_C2") (pintype "passive"))
      (node (ref "D(ESC)") (pin "C3") (pinfunction "C_C3") (pintype "passive"))
      (node (ref "D(\\\\)") (pin "C1") (pinfunction "C_C1") (pintype "passive"))
      (node (ref "D(\\\\)") (pin "C2") (pinfunction "C_C2") (pintype "passive"))
      (node (ref "D(\\\\)") (pin "C3") (pinfunction "C_C3") (pintype "passive"))
      (node (ref "D(~)") (pin "C1") (pinfunction "C_C1") (pintype "passive"))
      (node (ref "D(~)") (pin "C2") (pinfunction "C_C2") (pintype "passive"))
      (node (ref "D(~)") (pin "C3") (pinfunction "C_C3") (pintype "passive"))
      (node (ref "U$1") (pin "38") (pinfunction "PF5(ADC5)_38") (pintype "bidirectional"))
    )
    (net (code "157") (name "ROW2") (class "Default")
      (node (ref "D(DEL)") (pin "C1") (pinfunction "C_C1") (pintype "passive"))
      (node (ref "D(DEL)") (pin "C2") (pinfunction "C_C2") (pintype "passive"))
      (node (ref "D(DEL)") (pin "C3") (pinfunction "C_C3") (pintype "passive"))
      (node (ref "D(E)") (pin "C1") (pinfunction "C_C1") (pintype "passive"))
      (node (ref "D(E)") (pin "C2") (pinfunction "C_C2") (pintype "passive"))
      (node (ref "D(E)") (pin "C3") (pinfunction "C_C3") (pintype "passive"))
      (node (ref "D(I)") (pin "C1") (pinfunction "C_C1") (pintype "passive"))
      (node (ref "D(I)") (pin "C2") (pinfunction "C_C2") (pintype "passive"))
      (node (ref "D(I)") (pin "C3") (pinfunction "C_C3") (pintype "passive"))
      (node (ref "D(O)") (pin "C1") (pinfunction "C_C1") (pintype "passive"))
      (node (ref "D(O)") (pin "C2") (pinfunction "C_C2") (pintype "passive"))
      (node (ref "D(O)") (pin "C3") (pinfunction "C_C3") (pintype "passive"))
      (node (ref "D(P)") (pin "C1") (pinfunction "C_C1") (pintype "passive"))
      (node (ref "D(P)") (pin "C2") (pinfunction "C_C2") (pintype "passive"))
      (node (ref "D(P)") (pin "C3") (pinfunction "C_C3") (pintype "passive"))
      (node (ref "D(Q)") (pin "C1") (pinfunction "C_C1") (pintype "passive"))
      (node (ref "D(Q)") (pin "C2") (pinfunction "C_C2") (pintype "passive"))
      (node (ref "D(Q)") (pin "C3") (pinfunction "C_C3") (pintype "passive"))
      (node (ref "D(R)") (pin "C1") (pinfunction "C_C1") (pintype "passive"))
      (node (ref "D(R)") (pin "C2") (pinfunction "C_C2") (pintype "passive"))
      (node (ref "D(R)") (pin "C3") (pinfunction "C_C3") (pintype "passive"))
      (node (ref "D(T)") (pin "C1") (pinfunction "C_C1") (pintype "passive"))
      (node (ref "D(T)") (pin "C2") (pinfunction "C_C2") (pintype "passive"))
      (node (ref "D(T)") (pin "C3") (pinfunction "C_C3") (pintype "passive"))
      (node (ref "D(TAB)") (pin "C1") (pinfunction "C_C1") (pintype "passive"))
      (node (ref "D(TAB)") (pin "C2") (pinfunction "C_C2") (pintype "passive"))
      (node (ref "D(TAB)") (pin "C3") (pinfunction "C_C3") (pintype "passive"))
      (node (ref "D(U)") (pin "C1") (pinfunction "C_C1") (pintype "passive"))
      (node (ref "D(U)") (pin "C2") (pinfunction "C_C2") (pintype "passive"))
      (node (ref "D(U)") (pin "C3") (pinfunction "C_C3") (pintype "passive"))
      (node (ref "D(W)") (pin "C1") (pinfunction "C_C1") (pintype "passive"))
      (node (ref "D(W)") (pin "C2") (pinfunction "C_C2") (pintype "passive"))
      (node (ref "D(W)") (pin "C3") (pinfunction "C_C3") (pintype "passive"))
      (node (ref "D(Y)") (pin "C1") (pinfunction "C_C1") (pintype "passive"))
      (node (ref "D(Y)") (pin "C2") (pinfunction "C_C2") (pintype "passive"))
      (node (ref "D(Y)") (pin "C3") (pinfunction "C_C3") (pintype "passive"))
      (node (ref "D([)") (pin "C1") (pinfunction "C_C1") (pintype "passive"))
      (node (ref "D([)") (pin "C2") (pinfunction "C_C2") (pintype "passive"))
      (node (ref "D([)") (pin "C3") (pinfunction "C_C3") (pintype "passive"))
      (node (ref "D(])") (pin "C1") (pinfunction "C_C1") (pintype "passive"))
      (node (ref "D(])") (pin "C2") (pinfunction "C_C2") (pintype "passive"))
      (node (ref "D(])") (pin "C3") (pinfunction "C_C3") (pintype "passive"))
      (node (ref "U$1") (pin "37") (pinfunction "PF6(ADC6)_37") (pintype "bidirectional"))
    )
    (net (code "158") (name "ROW3") (class "Default")
      (node (ref "D(A)") (pin "C1") (pinfunction "C_C1") (pintype "passive"))
      (node (ref "D(A)") (pin "C2") (pinfunction "C_C2") (pintype "passive"))
      (node (ref "D(A)") (pin "C3") (pinfunction "C_C3") (pintype "passive"))
      (node (ref "D(CAPS)") (pin "C1") (pinfunction "C_C1") (pintype "passive"))
      (node (ref "D(CAPS)") (pin "C2") (pinfunction "C_C2") (pintype "passive"))
      (node (ref "D(CAPS)") (pin "C3") (pinfunction "C_C3") (pintype "passive"))
      (node (ref "D(COLON)") (pin "C1") (pinfunction "C_C1") (pintype "passive"))
      (node (ref "D(COLON)") (pin "C2") (pinfunction "C_C2") (pintype "passive"))
      (node (ref "D(COLON)") (pin "C3") (pinfunction "C_C3") (pintype "passive"))
      (node (ref "D(D)") (pin "C1") (pinfunction "C_C1") (pintype "passive"))
      (node (ref "D(D)") (pin "C2") (pinfunction "C_C2") (pintype "passive"))
      (node (ref "D(D)") (pin "C3") (pinfunction "C_C3") (pintype "passive"))
      (node (ref "D(ENTER)") (pin "C1") (pinfunction "C_C1") (pintype "passive"))
      (node (ref "D(ENTER)") (pin "C2") (pinfunction "C_C2") (pintype "passive"))
      (node (ref "D(ENTER)") (pin "C3") (pinfunction "C_C3") (pintype "passive"))
      (node (ref "D(F)") (pin "C1") (pinfunction "C_C1") (pintype "passive"))
      (node (ref "D(F)") (pin "C2") (pinfunction "C_C2") (pintype "passive"))
      (node (ref "D(F)") (pin "C3") (pinfunction "C_C3") (pintype "passive"))
      (node (ref "D(G)") (pin "C1") (pinfunction "C_C1") (pintype "passive"))
      (node (ref "D(G)") (pin "C2") (pinfunction "C_C2") (pintype "passive"))
      (node (ref "D(G)") (pin "C3") (pinfunction "C_C3") (pintype "passive"))
      (node (ref "D(H)") (pin "C1") (pinfunction "C_C1") (pintype "passive"))
      (node (ref "D(H)") (pin "C2") (pinfunction "C_C2") (pintype "passive"))
      (node (ref "D(H)") (pin "C3") (pinfunction "C_C3") (pintype "passive"))
      (node (ref "D(J)") (pin "C1") (pinfunction "C_C1") (pintype "passive"))
      (node (ref "D(J)") (pin "C2") (pinfunction "C_C2") (pintype "passive"))
      (node (ref "D(J)") (pin "C3") (pinfunction "C_C3") (pintype "passive"))
      (node (ref "D(K)") (pin "C1") (pinfunction "C_C1") (pintype "passive"))
      (node (ref "D(K)") (pin "C2") (pinfunction "C_C2") (pintype "passive"))
      (node (ref "D(K)") (pin "C3") (pinfunction "C_C3") (pintype "passive"))
      (node (ref "D(L)") (pin "C1") (pinfunction "C_C1") (pintype "passive"))
      (node (ref "D(L)") (pin "C2") (pinfunction "C_C2") (pintype "passive"))
      (node (ref "D(L)") (pin "C3") (pinfunction "C_C3") (pintype "passive"))
      (node (ref "D(QUOTE)") (pin "C1") (pinfunction "C_C1") (pintype "passive"))
      (node (ref "D(QUOTE)") (pin "C2") (pinfunction "C_C2") (pintype "passive"))
      (node (ref "D(QUOTE)") (pin "C3") (pinfunction "C_C3") (pintype "passive"))
      (node (ref "D(S)") (pin "C1") (pinfunction "C_C1") (pintype "passive"))
      (node (ref "D(S)") (pin "C2") (pinfunction "C_C2") (pintype "passive"))
      (node (ref "D(S)") (pin "C3") (pinfunction "C_C3") (pintype "passive"))
      (node (ref "U$1") (pin "36") (pinfunction "PF7(ADC7)_36") (pintype "bidirectional"))
    )
    (net (code "159") (name "ROW4") (class "Default")
      (node (ref "D(<)") (pin "C1") (pinfunction "C_C1") (pintype "passive"))
      (node (ref "D(<)") (pin "C2") (pinfunction "C_C2") (pintype "passive"))
      (node (ref "D(<)") (pin "C3") (pinfunction "C_C3") (pintype "passive"))
      (node (ref "D(>)") (pin "C1") (pinfunction "C_C1") (pintype "passive"))
      (node (ref "D(>)") (pin "C2") (pinfunction "C_C2") (pintype "passive"))
      (node (ref "D(>)") (pin "C3") (pinfunction "C_C3") (pintype "passive"))
      (node (ref "D(?)") (pin "C1") (pinfunction "C_C1") (pintype "passive"))
      (node (ref "D(?)") (pin "C2") (pinfunction "C_C2") (pintype "passive"))
      (node (ref "D(?)") (pin "C3") (pinfunction "C_C3") (pintype "passive"))
      (node (ref "D(B)") (pin "C1") (pinfunction "C_C1") (pintype "passive"))
      (node (ref "D(B)") (pin "C2") (pinfunction "C_C2") (pintype "passive"))
      (node (ref "D(B)") (pin "C3") (pinfunction "C_C3") (pintype "passive"))
      (node (ref "D(C)") (pin "C1") (pinfunction "C_C1") (pintype "passive"))
      (node (ref "D(C)") (pin "C2") (pinfunction "C_C2") (pintype "passive"))
      (node (ref "D(C)") (pin "C3") (pinfunction "C_C3") (pintype "passive"))
      (node (ref "D(FN)") (pin "C1") (pinfunction "C_C1") (pintype "passive"))
      (node (ref "D(FN)") (pin "C2") (pinfunction "C_C2") (pintype "passive"))
      (node (ref "D(FN)") (pin "C3") (pinfunction "C_C3") (pintype "passive"))
      (node (ref "D(LSHIFT)") (pin "C1") (pinfunction "C_C1") (pintype "passive"))
      (node (ref "D(LSHIFT)") (pin "C2") (pinfunction "C_C2") (pintype "passive"))
      (node (ref "D(LSHIFT)") (pin "C3") (pinfunction "C_C3") (pintype "passive"))
      (node (ref "D(M)") (pin "C1") (pinfunction "C_C1") (pintype "passive"))
      (node (ref "D(M)") (pin "C2") (pinfunction "C_C2") (pintype "passive"))
      (node (ref "D(M)") (pin "C3") (pinfunction "C_C3") (pintype "passive"))
      (node (ref "D(N)") (pin "C1") (pinfunction "C_C1") (pintype "passive"))
      (node (ref "D(N)") (pin "C2") (pinfunction "C_C2") (pintype "passive"))
      (node (ref "D(N)") (pin "C3") (pinfunction "C_C3") (pintype "passive"))
      (node (ref "D(RSHIFT)") (pin "C1") (pinfunction "C_C1") (pintype "passive"))
      (node (ref "D(RSHIFT)") (pin "C2") (pinfunction "C_C2") (pintype "passive"))
      (node (ref "D(RSHIFT)") (pin "C3") (pinfunction "C_C3") (pintype "passive"))
      (node (ref "D(V)") (pin "C1") (pinfunction "C_C1") (pintype "passive"))
      (node (ref "D(V)") (pin "C2") (pinfunction "C_C2") (pintype "passive"))
      (node (ref "D(V)") (pin "C3") (pinfunction "C_C3") (pintype "passive"))
      (node (ref "D(X)") (pin "C1") (pinfunction "C_C1") (pintype "passive"))
      (node (ref "D(X)") (pin "C2") (pinfunction "C_C2") (pintype "passive"))
      (node (ref "D(X)") (pin "C3") (pinfunction "C_C3") (pintype "passive"))
      (node (ref "D(Z)") (pin "C1") (pinfunction "C_C1") (pintype "passive"))
      (node (ref "D(Z)") (pin "C2") (pinfunction "C_C2") (pintype "passive"))
      (node (ref "D(Z)") (pin "C3") (pinfunction "C_C3") (pintype "passive"))
      (node (ref "U$1") (pin "40") (pinfunction "PF1(ADC1)_40") (pintype "bidirectional"))
    )
    (net (code "160") (name "ROW6") (class "Default")
      (node (ref "D(LALT)") (pin "C1") (pinfunction "C_C1") (pintype "passive"))
      (node (ref "D(LALT)") (pin "C2") (pinfunction "C_C2") (pintype "passive"))
      (node (ref "D(LALT)") (pin "C3") (pinfunction "C_C3") (pintype "passive"))
      (node (ref "D(LCTRL)") (pin "C1") (pinfunction "C_C1") (pintype "passive"))
      (node (ref "D(LCTRL)") (pin "C2") (pinfunction "C_C2") (pintype "passive"))
      (node (ref "D(LCTRL)") (pin "C3") (pinfunction "C_C3") (pintype "passive"))
      (node (ref "D(LSUPER)") (pin "C1") (pinfunction "C_C1") (pintype "passive"))
      (node (ref "D(LSUPER)") (pin "C2") (pinfunction "C_C2") (pintype "passive"))
      (node (ref "D(LSUPER)") (pin "C3") (pinfunction "C_C3") (pintype "passive"))
      (node (ref "D(RALT)") (pin "C1") (pinfunction "C_C1") (pintype "passive"))
      (node (ref "D(RALT)") (pin "C2") (pinfunction "C_C2") (pintype "passive"))
      (node (ref "D(RALT)") (pin "C3") (pinfunction "C_C3") (pintype "passive"))
      (node (ref "D(RCTRL)") (pin "C1") (pinfunction "C_C1") (pintype "passive"))
      (node (ref "D(RCTRL)") (pin "C2") (pinfunction "C_C2") (pintype "passive"))
      (node (ref "D(RCTRL)") (pin "C3") (pinfunction "C_C3") (pintype "passive"))
      (node (ref "D(RSUPER)") (pin "C1") (pinfunction "C_C1") (pintype "passive"))
      (node (ref "D(RSUPER)") (pin "C2") (pinfunction "C_C2") (pintype "passive"))
      (node (ref "D(RSUPER)") (pin "C3") (pinfunction "C_C3") (pintype "passive"))
      (node (ref "D(SPC)") (pin "C1") (pinfunction "C_C1") (pintype "passive"))
      (node (ref "D(SPC)") (pin "C2") (pinfunction "C_C2") (pintype "passive"))
      (node (ref "D(SPC)") (pin "C3") (pinfunction "C_C3") (pintype "passive"))
      (node (ref "U$1") (pin "25") (pinfunction "PD4(ADC8)_25") (pintype "bidirectional"))
    )
    (net (code "161") (name "VCC") (class "Default")
      (node (ref "C4") (pin "1") (pinfunction "1_1") (pintype "passive"))
      (node (ref "C5") (pin "1") (pinfunction "1_1") (pintype "passive"))
      (node (ref "C6") (pin "1") (pinfunction "1_1") (pintype "passive"))
      (node (ref "C7") (pin "1") (pinfunction "1_1") (pintype "passive"))
      (node (ref "C8") (pin "1") (pinfunction "1_1") (pintype "passive"))
      (node (ref "L(LSUPER)") (pin "B1") (pinfunction "2_B1") (pintype "passive"))
      (node (ref "L(LSUPER)") (pin "B2") (pinfunction "2_B2") (pintype "passive"))
      (node (ref "L(LSUPER)") (pin "B3") (pinfunction "2_B3") (pintype "passive"))
      (node (ref "R(+)") (pin "A1") (pinfunction "1_A1") (pintype "passive"))
      (node (ref "R(+)") (pin "A2") (pinfunction "1_A2") (pintype "passive"))
      (node (ref "R(+)") (pin "A3") (pinfunction "1_A3") (pintype "passive"))
      (node (ref "R(-)") (pin "A1") (pinfunction "1_A1") (pintype "passive"))
      (node (ref "R(-)") (pin "A2") (pinfunction "1_A2") (pintype "passive"))
      (node (ref "R(-)") (pin "A3") (pinfunction "1_A3") (pintype "passive"))
      (node (ref "R(0)") (pin "A1") (pinfunction "1_A1") (pintype "passive"))
      (node (ref "R(0)") (pin "A2") (pinfunction "1_A2") (pintype "passive"))
      (node (ref "R(0)") (pin "A3") (pinfunction "1_A3") (pintype "passive"))
      (node (ref "R(1)") (pin "A1") (pinfunction "1_A1") (pintype "passive"))
      (node (ref "R(1)") (pin "A2") (pinfunction "1_A2") (pintype "passive"))
      (node (ref "R(1)") (pin "A3") (pinfunction "1_A3") (pintype "passive"))
      (node (ref "R(2)") (pin "A1") (pinfunction "1_A1") (pintype "passive"))
      (node (ref "R(2)") (pin "A2") (pinfunction "1_A2") (pintype "passive"))
      (node (ref "R(2)") (pin "A3") (pinfunction "1_A3") (pintype "passive"))
      (node (ref "R(3)") (pin "A1") (pinfunction "1_A1") (pintype "passive"))
      (node (ref "R(3)") (pin "A2") (pinfunction "1_A2") (pintype "passive"))
      (node (ref "R(3)") (pin "A3") (pinfunction "1_A3") (pintype "passive"))
      (node (ref "R(4)") (pin "A1") (pinfunction "1_A1") (pintype "passive"))
      (node (ref "R(4)") (pin "A2") (pinfunction "1_A2") (pintype "passive"))
      (node (ref "R(4)") (pin "A3") (pinfunction "1_A3") (pintype "passive"))
      (node (ref "R(5)") (pin "A1") (pinfunction "1_A1") (pintype "passive"))
      (node (ref "R(5)") (pin "A2") (pinfunction "1_A2") (pintype "passive"))
      (node (ref "R(5)") (pin "A3") (pinfunction "1_A3") (pintype "passive"))
      (node (ref "R(6)") (pin "A1") (pinfunction "1_A1") (pintype "passive"))
      (node (ref "R(6)") (pin "A2") (pinfunction "1_A2") (pintype "passive"))
      (node (ref "R(6)") (pin "A3") (pinfunction "1_A3") (pintype "passive"))
      (node (ref "R(7)") (pin "A1") (pinfunction "1_A1") (pintype "passive"))
      (node (ref "R(7)") (pin "A2") (pinfunction "1_A2") (pintype "passive"))
      (node (ref "R(7)") (pin "A3") (pinfunction "1_A3") (pintype "passive"))
      (node (ref "R(8)") (pin "A1") (pinfunction "1_A1") (pintype "passive"))
      (node (ref "R(8)") (pin "A2") (pinfunction "1_A2") (pintype "passive"))
      (node (ref "R(8)") (pin "A3") (pinfunction "1_A3") (pintype "passive"))
      (node (ref "R(9)") (pin "A1") (pinfunction "1_A1") (pintype "passive"))
      (node (ref "R(9)") (pin "A2") (pinfunction "1_A2") (pintype "passive"))
      (node (ref "R(9)") (pin "A3") (pinfunction "1_A3") (pintype "passive"))
      (node (ref "R(<)") (pin "A1") (pinfunction "1_A1") (pintype "passive"))
      (node (ref "R(<)") (pin "A2") (pinfunction "1_A2") (pintype "passive"))
      (node (ref "R(<)") (pin "A3") (pinfunction "1_A3") (pintype "passive"))
      (node (ref "R(>)") (pin "A1") (pinfunction "1_A1") (pintype "passive"))
      (node (ref "R(>)") (pin "A2") (pinfunction "1_A2") (pintype "passive"))
      (node (ref "R(>)") (pin "A3") (pinfunction "1_A3") (pintype "passive"))
      (node (ref "R(?)") (pin "A1") (pinfunction "1_A1") (pintype "passive"))
      (node (ref "R(?)") (pin "A2") (pinfunction "1_A2") (pintype "passive"))
      (node (ref "R(?)") (pin "A3") (pinfunction "1_A3") (pintype "passive"))
      (node (ref "R(A)") (pin "A1") (pinfunction "1_A1") (pintype "passive"))
      (node (ref "R(A)") (pin "A2") (pinfunction "1_A2") (pintype "passive"))
      (node (ref "R(A)") (pin "A3") (pinfunction "1_A3") (pintype "passive"))
      (node (ref "R(B)") (pin "A1") (pinfunction "1_A1") (pintype "passive"))
      (node (ref "R(B)") (pin "A2") (pinfunction "1_A2") (pintype "passive"))
      (node (ref "R(B)") (pin "A3") (pinfunction "1_A3") (pintype "passive"))
      (node (ref "R(C)") (pin "A1") (pinfunction "1_A1") (pintype "passive"))
      (node (ref "R(C)") (pin "A2") (pinfunction "1_A2") (pintype "passive"))
      (node (ref "R(C)") (pin "A3") (pinfunction "1_A3") (pintype "passive"))
      (node (ref "R(CAPS)") (pin "A1") (pinfunction "1_A1") (pintype "passive"))
      (node (ref "R(CAPS)") (pin "A2") (pinfunction "1_A2") (pintype "passive"))
      (node (ref "R(CAPS)") (pin "A3") (pinfunction "1_A3") (pintype "passive"))
      (node (ref "R(COLON)") (pin "A1") (pinfunction "1_A1") (pintype "passive"))
      (node (ref "R(COLON)") (pin "A2") (pinfunction "1_A2") (pintype "passive"))
      (node (ref "R(COLON)") (pin "A3") (pinfunction "1_A3") (pintype "passive"))
      (node (ref "R(D)") (pin "A1") (pinfunction "1_A1") (pintype "passive"))
      (node (ref "R(D)") (pin "A2") (pinfunction "1_A2") (pintype "passive"))
      (node (ref "R(D)") (pin "A3") (pinfunction "1_A3") (pintype "passive"))
      (node (ref "R(DEL)") (pin "A1") (pinfunction "1_A1") (pintype "passive"))
      (node (ref "R(DEL)") (pin "A2") (pinfunction "1_A2") (pintype "passive"))
      (node (ref "R(DEL)") (pin "A3") (pinfunction "1_A3") (pintype "passive"))
      (node (ref "R(E)") (pin "A1") (pinfunction "1_A1") (pintype "passive"))
      (node (ref "R(E)") (pin "A2") (pinfunction "1_A2") (pintype "passive"))
      (node (ref "R(E)") (pin "A3") (pinfunction "1_A3") (pintype "passive"))
      (node (ref "R(ENTER)") (pin "A1") (pinfunction "1_A1") (pintype "passive"))
      (node (ref "R(ENTER)") (pin "A2") (pinfunction "1_A2") (pintype "passive"))
      (node (ref "R(ENTER)") (pin "A3") (pinfunction "1_A3") (pintype "passive"))
      (node (ref "R(ESC)") (pin "A1") (pinfunction "1_A1") (pintype "passive"))
      (node (ref "R(ESC)") (pin "A2") (pinfunction "1_A2") (pintype "passive"))
      (node (ref "R(ESC)") (pin "A3") (pinfunction "1_A3") (pintype "passive"))
      (node (ref "R(F)") (pin "A1") (pinfunction "1_A1") (pintype "passive"))
      (node (ref "R(F)") (pin "A2") (pinfunction "1_A2") (pintype "passive"))
      (node (ref "R(F)") (pin "A3") (pinfunction "1_A3") (pintype "passive"))
      (node (ref "R(FN)") (pin "A1") (pinfunction "1_A1") (pintype "passive"))
      (node (ref "R(FN)") (pin "A2") (pinfunction "1_A2") (pintype "passive"))
      (node (ref "R(FN)") (pin "A3") (pinfunction "1_A3") (pintype "passive"))
      (node (ref "R(G)") (pin "A1") (pinfunction "1_A1") (pintype "passive"))
      (node (ref "R(G)") (pin "A2") (pinfunction "1_A2") (pintype "passive"))
      (node (ref "R(G)") (pin "A3") (pinfunction "1_A3") (pintype "passive"))
      (node (ref "R(H)") (pin "A1") (pinfunction "1_A1") (pintype "passive"))
      (node (ref "R(H)") (pin "A2") (pinfunction "1_A2") (pintype "passive"))
      (node (ref "R(H)") (pin "A3") (pinfunction "1_A3") (pintype "passive"))
      (node (ref "R(I)") (pin "A1") (pinfunction "1_A1") (pintype "passive"))
      (node (ref "R(I)") (pin "A2") (pinfunction "1_A2") (pintype "passive"))
      (node (ref "R(I)") (pin "A3") (pinfunction "1_A3") (pintype "passive"))
      (node (ref "R(J)") (pin "A1") (pinfunction "1_A1") (pintype "passive"))
      (node (ref "R(J)") (pin "A2") (pinfunction "1_A2") (pintype "passive"))
      (node (ref "R(J)") (pin "A3") (pinfunction "1_A3") (pintype "passive"))
      (node (ref "R(K)") (pin "A1") (pinfunction "1_A1") (pintype "passive"))
      (node (ref "R(K)") (pin "A2") (pinfunction "1_A2") (pintype "passive"))
      (node (ref "R(K)") (pin "A3") (pinfunction "1_A3") (pintype "passive"))
      (node (ref "R(L)") (pin "A1") (pinfunction "1_A1") (pintype "passive"))
      (node (ref "R(L)") (pin "A2") (pinfunction "1_A2") (pintype "passive"))
      (node (ref "R(L)") (pin "A3") (pinfunction "1_A3") (pintype "passive"))
      (node (ref "R(LALT)") (pin "B1") (pinfunction "2_B1") (pintype "passive"))
      (node (ref "R(LALT)") (pin "B2") (pinfunction "2_B2") (pintype "passive"))
      (node (ref "R(LALT)") (pin "B3") (pinfunction "2_B3") (pintype "passive"))
      (node (ref "R(LCTRL)") (pin "B1") (pinfunction "2_B1") (pintype "passive"))
      (node (ref "R(LCTRL)") (pin "B2") (pinfunction "2_B2") (pintype "passive"))
      (node (ref "R(LCTRL)") (pin "B3") (pinfunction "2_B3") (pintype "passive"))
      (node (ref "R(LSHIFT)") (pin "A1") (pinfunction "1_A1") (pintype "passive"))
      (node (ref "R(LSHIFT)") (pin "A2") (pinfunction "1_A2") (pintype "passive"))
      (node (ref "R(LSHIFT)") (pin "A3") (pinfunction "1_A3") (pintype "passive"))
      (node (ref "R(M)") (pin "A1") (pinfunction "1_A1") (pintype "passive"))
      (node (ref "R(M)") (pin "A2") (pinfunction "1_A2") (pintype "passive"))
      (node (ref "R(M)") (pin "A3") (pinfunction "1_A3") (pintype "passive"))
      (node (ref "R(N)") (pin "A1") (pinfunction "1_A1") (pintype "passive"))
      (node (ref "R(N)") (pin "A2") (pinfunction "1_A2") (pintype "passive"))
      (node (ref "R(N)") (pin "A3") (pinfunction "1_A3") (pintype "passive"))
      (node (ref "R(O)") (pin "A1") (pinfunction "1_A1") (pintype "passive"))
      (node (ref "R(O)") (pin "A2") (pinfunction "1_A2") (pintype "passive"))
      (node (ref "R(O)") (pin "A3") (pinfunction "1_A3") (pintype "passive"))
      (node (ref "R(P)") (pin "A1") (pinfunction "1_A1") (pintype "passive"))
      (node (ref "R(P)") (pin "A2") (pinfunction "1_A2") (pintype "passive"))
      (node (ref "R(P)") (pin "A3") (pinfunction "1_A3") (pintype "passive"))
      (node (ref "R(Q)") (pin "A1") (pinfunction "1_A1") (pintype "passive"))
      (node (ref "R(Q)") (pin "A2") (pinfunction "1_A2") (pintype "passive"))
      (node (ref "R(Q)") (pin "A3") (pinfunction "1_A3") (pintype "passive"))
      (node (ref "R(QUOTE)") (pin "A1") (pinfunction "1_A1") (pintype "passive"))
      (node (ref "R(QUOTE)") (pin "A2") (pinfunction "1_A2") (pintype "passive"))
      (node (ref "R(QUOTE)") (pin "A3") (pinfunction "1_A3") (pintype "passive"))
      (node (ref "R(R)") (pin "A1") (pinfunction "1_A1") (pintype "passive"))
      (node (ref "R(R)") (pin "A2") (pinfunction "1_A2") (pintype "passive"))
      (node (ref "R(R)") (pin "A3") (pinfunction "1_A3") (pintype "passive"))
      (node (ref "R(RALT)") (pin "A1") (pinfunction "1_A1") (pintype "passive"))
      (node (ref "R(RALT)") (pin "A2") (pinfunction "1_A2") (pintype "passive"))
      (node (ref "R(RALT)") (pin "A3") (pinfunction "1_A3") (pintype "passive"))
      (node (ref "R(RCTRL)") (pin "A1") (pinfunction "1_A1") (pintype "passive"))
      (node (ref "R(RCTRL)") (pin "A2") (pinfunction "1_A2") (pintype "passive"))
      (node (ref "R(RCTRL)") (pin "A3") (pinfunction "1_A3") (pintype "passive"))
      (node (ref "R(RSHIFT)") (pin "A1") (pinfunction "1_A1") (pintype "passive"))
      (node (ref "R(RSHIFT)") (pin "A2") (pinfunction "1_A2") (pintype "passive"))
      (node (ref "R(RSHIFT)") (pin "A3") (pinfunction "1_A3") (pintype "passive"))
      (node (ref "R(RSUPER)") (pin "A1") (pinfunction "1_A1") (pintype "passive"))
      (node (ref "R(RSUPER)") (pin "A2") (pinfunction "1_A2") (pintype "passive"))
      (node (ref "R(RSUPER)") (pin "A3") (pinfunction "1_A3") (pintype "passive"))
      (node (ref "R(S)") (pin "A1") (pinfunction "1_A1") (pintype "passive"))
      (node (ref "R(S)") (pin "A2") (pinfunction "1_A2") (pintype "passive"))
      (node (ref "R(S)") (pin "A3") (pinfunction "1_A3") (pintype "passive"))
      (node (ref "R(SPC)") (pin "A1") (pinfunction "1_A1") (pintype "passive"))
      (node (ref "R(SPC)") (pin "A2") (pinfunction "1_A2") (pintype "passive"))
      (node (ref "R(SPC)") (pin "A3") (pinfunction "1_A3") (pintype "passive"))
      (node (ref "R(T)") (pin "A1") (pinfunction "1_A1") (pintype "passive"))
      (node (ref "R(T)") (pin "A2") (pinfunction "1_A2") (pintype "passive"))
      (node (ref "R(T)") (pin "A3") (pinfunction "1_A3") (pintype "passive"))
      (node (ref "R(TAB)") (pin "A1") (pinfunction "1_A1") (pintype "passive"))
      (node (ref "R(TAB)") (pin "A2") (pinfunction "1_A2") (pintype "passive"))
      (node (ref "R(TAB)") (pin "A3") (pinfunction "1_A3") (pintype "passive"))
      (node (ref "R(U)") (pin "A1") (pinfunction "1_A1") (pintype "passive"))
      (node (ref "R(U)") (pin "A2") (pinfunction "1_A2") (pintype "passive"))
      (node (ref "R(U)") (pin "A3") (pinfunction "1_A3") (pintype "passive"))
      (node (ref "R(V)") (pin "A1") (pinfunction "1_A1") (pintype "passive"))
      (node (ref "R(V)") (pin "A2") (pinfunction "1_A2") (pintype "passive"))
      (node (ref "R(V)") (pin "A3") (pinfunction "1_A3") (pintype "passive"))
      (node (ref "R(W)") (pin "A1") (pinfunction "1_A1") (pintype "passive"))
      (node (ref "R(W)") (pin "A2") (pinfunction "1_A2") (pintype "passive"))
      (node (ref "R(W)") (pin "A3") (pinfunction "1_A3") (pintype "passive"))
      (node (ref "R(X)") (pin "A1") (pinfunction "1_A1") (pintype "passive"))
      (node (ref "R(X)") (pin "A2") (pinfunction "1_A2") (pintype "passive"))
      (node (ref "R(X)") (pin "A3") (pinfunction "1_A3") (pintype "passive"))
      (node (ref "R(Y)") (pin "A1") (pinfunction "1_A1") (pintype "passive"))
      (node (ref "R(Y)") (pin "A2") (pinfunction "1_A2") (pintype "passive"))
      (node (ref "R(Y)") (pin "A3") (pinfunction "1_A3") (pintype "passive"))
      (node (ref "R(Z)") (pin "A1") (pinfunction "1_A1") (pintype "passive"))
      (node (ref "R(Z)") (pin "A2") (pinfunction "1_A2") (pintype "passive"))
      (node (ref "R(Z)") (pin "A3") (pinfunction "1_A3") (pintype "passive"))
      (node (ref "R([)") (pin "A1") (pinfunction "1_A1") (pintype "passive"))
      (node (ref "R([)") (pin "A2") (pinfunction "1_A2") (pintype "passive"))
      (node (ref "R([)") (pin "A3") (pinfunction "1_A3") (pintype "passive"))
      (node (ref "R(\\\\)") (pin "A1") (pinfunction "1_A1") (pintype "passive"))
      (node (ref "R(\\\\)") (pin "A2") (pinfunction "1_A2") (pintype "passive"))
      (node (ref "R(\\\\)") (pin "A3") (pinfunction "1_A3") (pintype "passive"))
      (node (ref "R(])") (pin "A1") (pinfunction "1_A1") (pintype "passive"))
      (node (ref "R(])") (pin "A2") (pinfunction "1_A2") (pintype "passive"))
      (node (ref "R(])") (pin "A3") (pinfunction "1_A3") (pintype "passive"))
      (node (ref "R(~)") (pin "A1") (pinfunction "1_A1") (pintype "passive"))
      (node (ref "R(~)") (pin "A2") (pinfunction "1_A2") (pintype "passive"))
      (node (ref "R(~)") (pin "A3") (pinfunction "1_A3") (pintype "passive"))
      (node (ref "R3") (pin "1") (pinfunction "1_1") (pintype "passive"))
      (node (ref "U$1") (pin "14") (pinfunction "VCC_14") (pintype "bidirectional"))
      (node (ref "U$1") (pin "2") (pinfunction "UVCC_2") (pintype "bidirectional"))
      (node (ref "U$1") (pin "24") (pinfunction "AVCC_24") (pintype "bidirectional"))
      (node (ref "U$1") (pin "34") (pinfunction "VCC_34") (pintype "bidirectional"))
      (node (ref "U$1") (pin "44") (pinfunction "AVCC_44") (pintype "bidirectional"))
      (node (ref "U$1") (pin "7") (pinfunction "VBUS_7") (pintype "bidirectional"))
      (node (ref "X1") (pin "1") (pinfunction "1_1") (pintype "input"))
    )
    (net (code "162") (name "unconnected-(K(SPC)-PadLED-)") (class "Default")
      (node (ref "K(SPC)") (pin "LED-") (pinfunction "LED-_LED-") (pintype "bidirectional"))
    )
    (net (code "163") (name "unconnected-(U$2-P-Pad1)") (class "Default")
      (node (ref "U$2") (pin "1") (pinfunction "P_1") (pintype "passive"))
    )
    (net (code "164") (name "unconnected-(U$3-PadP$1)") (class "Default")
      (node (ref "U$3") (pin "P$1") (pinfunction "P$1_P$1") (pintype "bidirectional"))
    )
    (net (code "165") (name "unconnected-(U$4-PadP$1)") (class "Default")
      (node (ref "U$4") (pin "P$1") (pinfunction "P$1_P$1") (pintype "bidirectional"))
    )
    (net (code "166") (name "unconnected-(U$5-PadP$1)") (class "Default")
      (node (ref "U$5") (pin "P$1") (pinfunction "P$1_P$1") (pintype "bidirectional"))
    )
    (net (code "167") (name "unconnected-(U$6-PadP$1)") (class "Default")
      (node (ref "U$6") (pin "P$1") (pinfunction "P$1_P$1") (pintype "bidirectional"))
    )
  )
)
